# iso_lvds_rx.net
KiCad netlist of a schematic drawn in Altium Designer
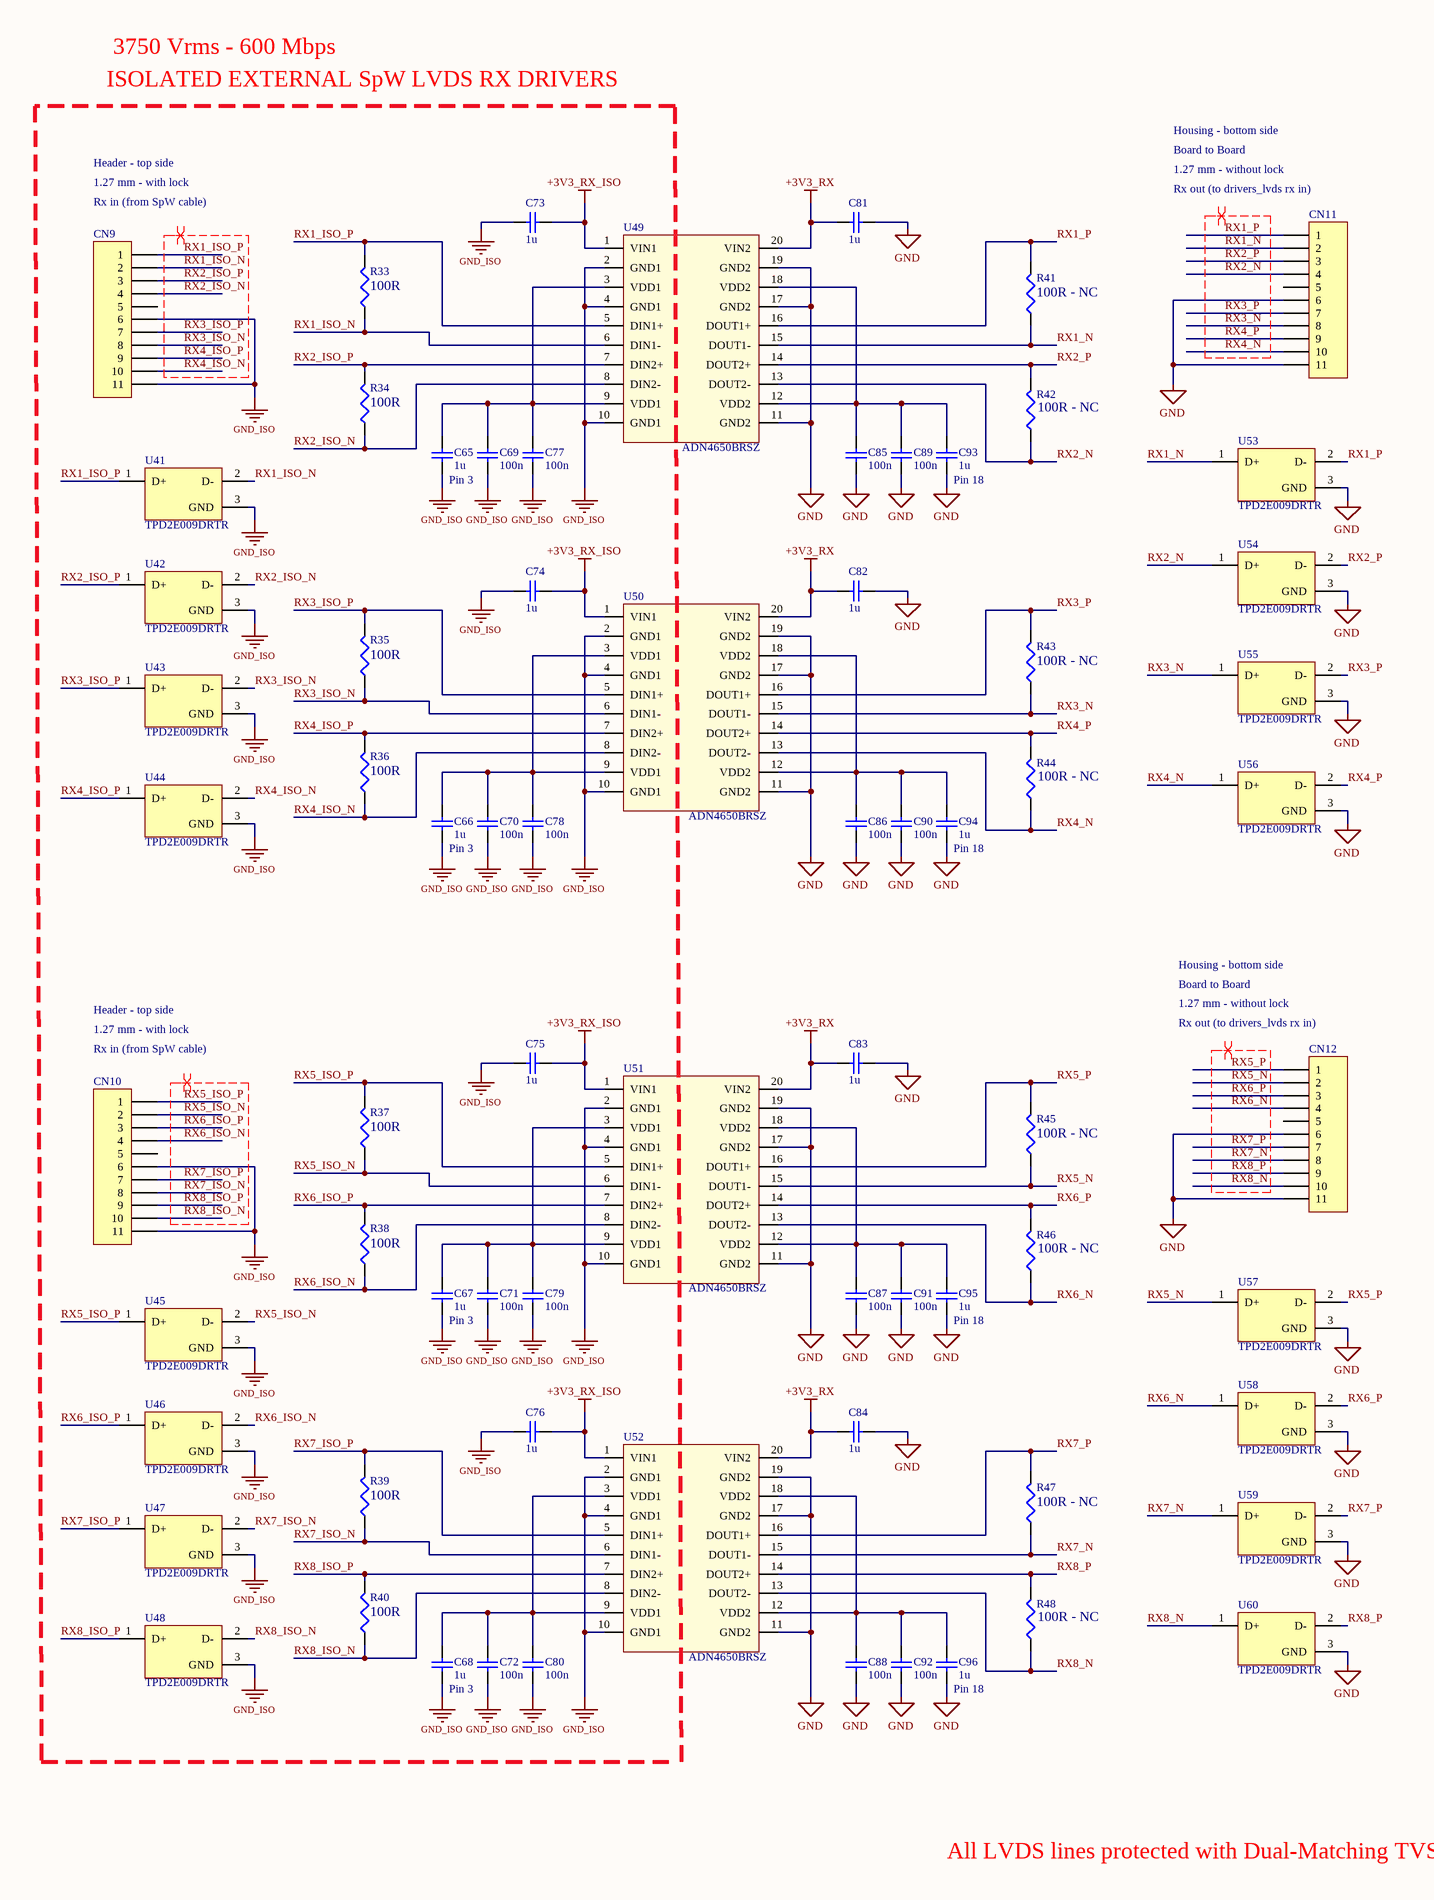
[diagram p0: iso_lvds_rx.SchDoc, left]
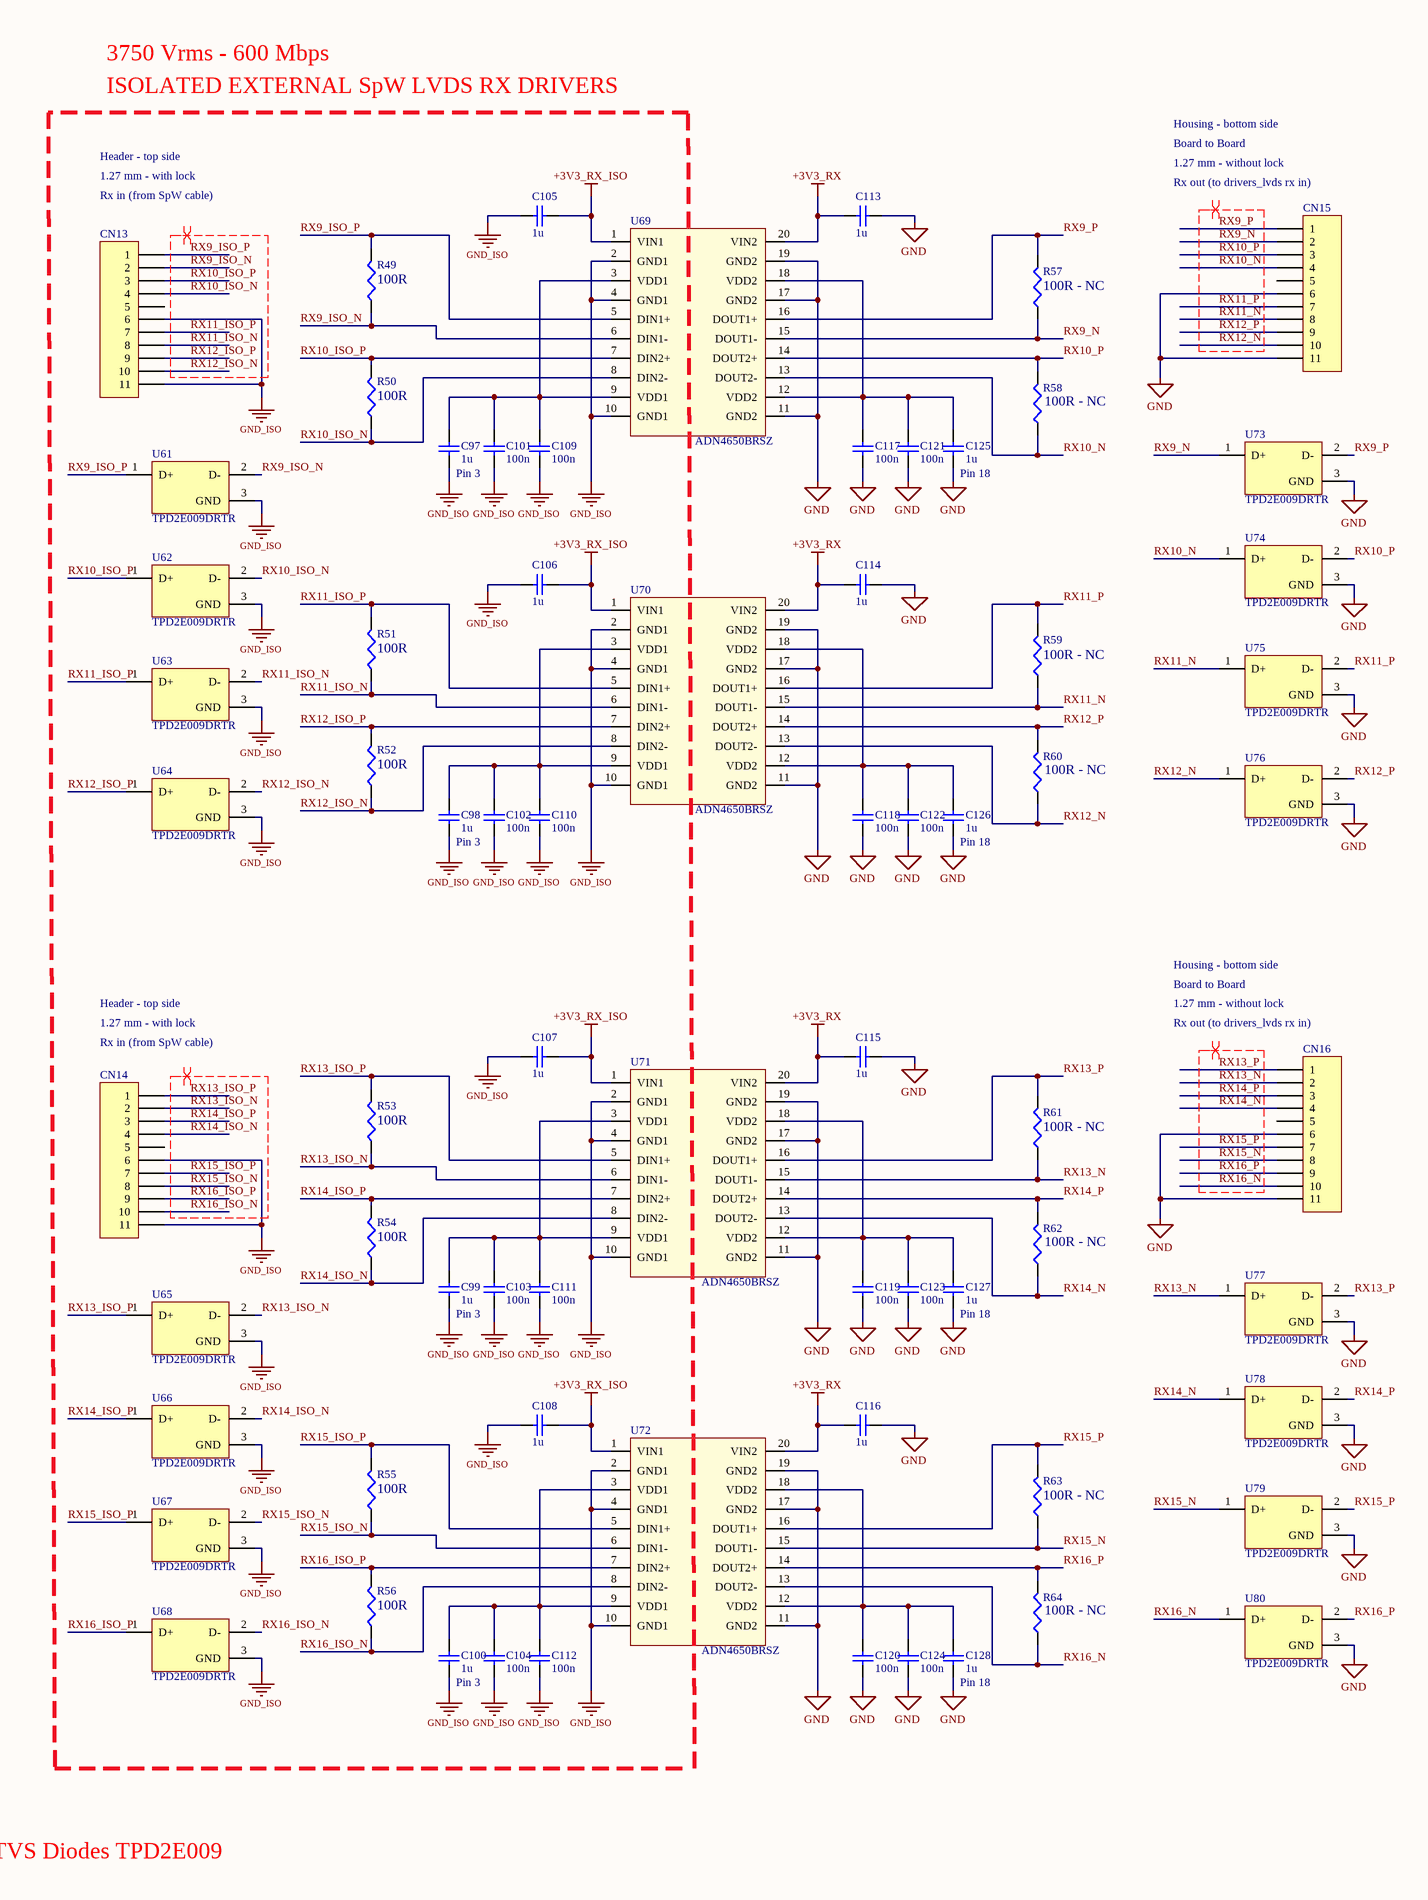
[diagram p1: iso_lvds_rx.SchDoc, right]

(export (version "E")
  (design (tool "Eeschema 10.0.6"))
  (components
    (comp (ref "C65")
      (value "Capacitor Cerâmico SMD")
      (footprint "0402-cap")
      (fields (field (name "VALOR") "1u"))
      (libsource (lib "Miscellaneous Devices") (part "Capacitor Cerâmico SMD"))
    )
    (comp (ref "C66")
      (value "Capacitor Cerâmico SMD")
      (footprint "0402-cap")
      (fields (field (name "VALOR") "1u"))
      (libsource (lib "Miscellaneous Devices") (part "Capacitor Cerâmico SMD"))
    )
    (comp (ref "C67")
      (value "Capacitor Cerâmico SMD")
      (footprint "0402-cap")
      (fields (field (name "VALOR") "1u"))
      (libsource (lib "Miscellaneous Devices") (part "Capacitor Cerâmico SMD"))
    )
    (comp (ref "C68")
      (value "Capacitor Cerâmico SMD")
      (footprint "0402-cap")
      (fields (field (name "VALOR") "1u"))
      (libsource (lib "Miscellaneous Devices") (part "Capacitor Cerâmico SMD"))
    )
    (comp (ref "C69")
      (value "Capacitor Cerâmico SMD")
      (footprint "0402-cap")
      (fields (field (name "VALOR") "100n"))
      (libsource (lib "Miscellaneous Devices") (part "Capacitor Cerâmico SMD"))
    )
    (comp (ref "C70")
      (value "Capacitor Cerâmico SMD")
      (footprint "0402-cap")
      (fields (field (name "VALOR") "100n"))
      (libsource (lib "Miscellaneous Devices") (part "Capacitor Cerâmico SMD"))
    )
    (comp (ref "C71")
      (value "Capacitor Cerâmico SMD")
      (footprint "0402-cap")
      (fields (field (name "VALOR") "100n"))
      (libsource (lib "Miscellaneous Devices") (part "Capacitor Cerâmico SMD"))
    )
    (comp (ref "C72")
      (value "Capacitor Cerâmico SMD")
      (footprint "0402-cap")
      (fields (field (name "VALOR") "100n"))
      (libsource (lib "Miscellaneous Devices") (part "Capacitor Cerâmico SMD"))
    )
    (comp (ref "C73")
      (value "Capacitor Cerâmico SMD")
      (footprint "0402-cap")
      (fields (field (name "VALOR") "1u"))
      (libsource (lib "Miscellaneous Devices") (part "Capacitor Cerâmico SMD"))
    )
    (comp (ref "C74")
      (value "Capacitor Cerâmico SMD")
      (footprint "0402-cap")
      (fields (field (name "VALOR") "1u"))
      (libsource (lib "Miscellaneous Devices") (part "Capacitor Cerâmico SMD"))
    )
    (comp (ref "C75")
      (value "Capacitor Cerâmico SMD")
      (footprint "0402-cap")
      (fields (field (name "VALOR") "1u"))
      (libsource (lib "Miscellaneous Devices") (part "Capacitor Cerâmico SMD"))
    )
    (comp (ref "C76")
      (value "Capacitor Cerâmico SMD")
      (footprint "0402-cap")
      (fields (field (name "VALOR") "1u"))
      (libsource (lib "Miscellaneous Devices") (part "Capacitor Cerâmico SMD"))
    )
    (comp (ref "C77")
      (value "Capacitor Cerâmico SMD")
      (footprint "0402-cap")
      (fields (field (name "VALOR") "100n"))
      (libsource (lib "Miscellaneous Devices") (part "Capacitor Cerâmico SMD"))
    )
    (comp (ref "C78")
      (value "Capacitor Cerâmico SMD")
      (footprint "0402-cap")
      (fields (field (name "VALOR") "100n"))
      (libsource (lib "Miscellaneous Devices") (part "Capacitor Cerâmico SMD"))
    )
    (comp (ref "C79")
      (value "Capacitor Cerâmico SMD")
      (footprint "0402-cap")
      (fields (field (name "VALOR") "100n"))
      (libsource (lib "Miscellaneous Devices") (part "Capacitor Cerâmico SMD"))
    )
    (comp (ref "C80")
      (value "Capacitor Cerâmico SMD")
      (footprint "0402-cap")
      (fields (field (name "VALOR") "100n"))
      (libsource (lib "Miscellaneous Devices") (part "Capacitor Cerâmico SMD"))
    )
    (comp (ref "C81")
      (value "Capacitor Cerâmico SMD")
      (footprint "0402-cap")
      (fields (field (name "VALOR") "1u"))
      (libsource (lib "Miscellaneous Devices") (part "Capacitor Cerâmico SMD"))
    )
    (comp (ref "C82")
      (value "Capacitor Cerâmico SMD")
      (footprint "0402-cap")
      (fields (field (name "VALOR") "1u"))
      (libsource (lib "Miscellaneous Devices") (part "Capacitor Cerâmico SMD"))
    )
    (comp (ref "C83")
      (value "Capacitor Cerâmico SMD")
      (footprint "0402-cap")
      (fields (field (name "VALOR") "1u"))
      (libsource (lib "Miscellaneous Devices") (part "Capacitor Cerâmico SMD"))
    )
    (comp (ref "C84")
      (value "Capacitor Cerâmico SMD")
      (footprint "0402-cap")
      (fields (field (name "VALOR") "1u"))
      (libsource (lib "Miscellaneous Devices") (part "Capacitor Cerâmico SMD"))
    )
    (comp (ref "C85")
      (value "Capacitor Cerâmico SMD")
      (footprint "0402-cap")
      (fields (field (name "VALOR") "100n"))
      (libsource (lib "Miscellaneous Devices") (part "Capacitor Cerâmico SMD"))
    )
    (comp (ref "C86")
      (value "Capacitor Cerâmico SMD")
      (footprint "0402-cap")
      (fields (field (name "VALOR") "100n"))
      (libsource (lib "Miscellaneous Devices") (part "Capacitor Cerâmico SMD"))
    )
    (comp (ref "C87")
      (value "Capacitor Cerâmico SMD")
      (footprint "0402-cap")
      (fields (field (name "VALOR") "100n"))
      (libsource (lib "Miscellaneous Devices") (part "Capacitor Cerâmico SMD"))
    )
    (comp (ref "C88")
      (value "Capacitor Cerâmico SMD")
      (footprint "0402-cap")
      (fields (field (name "VALOR") "100n"))
      (libsource (lib "Miscellaneous Devices") (part "Capacitor Cerâmico SMD"))
    )
    (comp (ref "C89")
      (value "Capacitor Cerâmico SMD")
      (footprint "0402-cap")
      (fields (field (name "VALOR") "100n"))
      (libsource (lib "Miscellaneous Devices") (part "Capacitor Cerâmico SMD"))
    )
    (comp (ref "C90")
      (value "Capacitor Cerâmico SMD")
      (footprint "0402-cap")
      (fields (field (name "VALOR") "100n"))
      (libsource (lib "Miscellaneous Devices") (part "Capacitor Cerâmico SMD"))
    )
    (comp (ref "C91")
      (value "Capacitor Cerâmico SMD")
      (footprint "0402-cap")
      (fields (field (name "VALOR") "100n"))
      (libsource (lib "Miscellaneous Devices") (part "Capacitor Cerâmico SMD"))
    )
    (comp (ref "C92")
      (value "Capacitor Cerâmico SMD")
      (footprint "0402-cap")
      (fields (field (name "VALOR") "100n"))
      (libsource (lib "Miscellaneous Devices") (part "Capacitor Cerâmico SMD"))
    )
    (comp (ref "C93")
      (value "Capacitor Cerâmico SMD")
      (footprint "0402-cap")
      (fields (field (name "VALOR") "1u"))
      (libsource (lib "Miscellaneous Devices") (part "Capacitor Cerâmico SMD"))
    )
    (comp (ref "C94")
      (value "Capacitor Cerâmico SMD")
      (footprint "0402-cap")
      (fields (field (name "VALOR") "1u"))
      (libsource (lib "Miscellaneous Devices") (part "Capacitor Cerâmico SMD"))
    )
    (comp (ref "C95")
      (value "Capacitor Cerâmico SMD")
      (footprint "0402-cap")
      (fields (field (name "VALOR") "1u"))
      (libsource (lib "Miscellaneous Devices") (part "Capacitor Cerâmico SMD"))
    )
    (comp (ref "C96")
      (value "Capacitor Cerâmico SMD")
      (footprint "0402-cap")
      (fields (field (name "VALOR") "1u"))
      (libsource (lib "Miscellaneous Devices") (part "Capacitor Cerâmico SMD"))
    )
    (comp (ref "C97")
      (value "Capacitor Cerâmico SMD")
      (footprint "0402-cap")
      (fields (field (name "VALOR") "1u"))
      (libsource (lib "Miscellaneous Devices") (part "Capacitor Cerâmico SMD"))
    )
    (comp (ref "C98")
      (value "Capacitor Cerâmico SMD")
      (footprint "0402-cap")
      (fields (field (name "VALOR") "1u"))
      (libsource (lib "Miscellaneous Devices") (part "Capacitor Cerâmico SMD"))
    )
    (comp (ref "C99")
      (value "Capacitor Cerâmico SMD")
      (footprint "0402-cap")
      (fields (field (name "VALOR") "1u"))
      (libsource (lib "Miscellaneous Devices") (part "Capacitor Cerâmico SMD"))
    )
    (comp (ref "C100")
      (value "Capacitor Cerâmico SMD")
      (footprint "0402-cap")
      (fields (field (name "VALOR") "1u"))
      (libsource (lib "Miscellaneous Devices") (part "Capacitor Cerâmico SMD"))
    )
    (comp (ref "C101")
      (value "Capacitor Cerâmico SMD")
      (footprint "0402-cap")
      (fields (field (name "VALOR") "100n"))
      (libsource (lib "Miscellaneous Devices") (part "Capacitor Cerâmico SMD"))
    )
    (comp (ref "C102")
      (value "Capacitor Cerâmico SMD")
      (footprint "0402-cap")
      (fields (field (name "VALOR") "100n"))
      (libsource (lib "Miscellaneous Devices") (part "Capacitor Cerâmico SMD"))
    )
    (comp (ref "C103")
      (value "Capacitor Cerâmico SMD")
      (footprint "0402-cap")
      (fields (field (name "VALOR") "100n"))
      (libsource (lib "Miscellaneous Devices") (part "Capacitor Cerâmico SMD"))
    )
    (comp (ref "C104")
      (value "Capacitor Cerâmico SMD")
      (footprint "0402-cap")
      (fields (field (name "VALOR") "100n"))
      (libsource (lib "Miscellaneous Devices") (part "Capacitor Cerâmico SMD"))
    )
    (comp (ref "C105")
      (value "Capacitor Cerâmico SMD")
      (footprint "0402-cap")
      (fields (field (name "VALOR") "1u"))
      (libsource (lib "Miscellaneous Devices") (part "Capacitor Cerâmico SMD"))
    )
    (comp (ref "C106")
      (value "Capacitor Cerâmico SMD")
      (footprint "0402-cap")
      (fields (field (name "VALOR") "1u"))
      (libsource (lib "Miscellaneous Devices") (part "Capacitor Cerâmico SMD"))
    )
    (comp (ref "C107")
      (value "Capacitor Cerâmico SMD")
      (footprint "0402-cap")
      (fields (field (name "VALOR") "1u"))
      (libsource (lib "Miscellaneous Devices") (part "Capacitor Cerâmico SMD"))
    )
    (comp (ref "C108")
      (value "Capacitor Cerâmico SMD")
      (footprint "0402-cap")
      (fields (field (name "VALOR") "1u"))
      (libsource (lib "Miscellaneous Devices") (part "Capacitor Cerâmico SMD"))
    )
    (comp (ref "C109")
      (value "Capacitor Cerâmico SMD")
      (footprint "0402-cap")
      (fields (field (name "VALOR") "100n"))
      (libsource (lib "Miscellaneous Devices") (part "Capacitor Cerâmico SMD"))
    )
    (comp (ref "C110")
      (value "Capacitor Cerâmico SMD")
      (footprint "0402-cap")
      (fields (field (name "VALOR") "100n"))
      (libsource (lib "Miscellaneous Devices") (part "Capacitor Cerâmico SMD"))
    )
    (comp (ref "C111")
      (value "Capacitor Cerâmico SMD")
      (footprint "0402-cap")
      (fields (field (name "VALOR") "100n"))
      (libsource (lib "Miscellaneous Devices") (part "Capacitor Cerâmico SMD"))
    )
    (comp (ref "C112")
      (value "Capacitor Cerâmico SMD")
      (footprint "0402-cap")
      (fields (field (name "VALOR") "100n"))
      (libsource (lib "Miscellaneous Devices") (part "Capacitor Cerâmico SMD"))
    )
    (comp (ref "C113")
      (value "Capacitor Cerâmico SMD")
      (footprint "0402-cap")
      (fields (field (name "VALOR") "1u"))
      (libsource (lib "Miscellaneous Devices") (part "Capacitor Cerâmico SMD"))
    )
    (comp (ref "C114")
      (value "Capacitor Cerâmico SMD")
      (footprint "0402-cap")
      (fields (field (name "VALOR") "1u"))
      (libsource (lib "Miscellaneous Devices") (part "Capacitor Cerâmico SMD"))
    )
    (comp (ref "C115")
      (value "Capacitor Cerâmico SMD")
      (footprint "0402-cap")
      (fields (field (name "VALOR") "1u"))
      (libsource (lib "Miscellaneous Devices") (part "Capacitor Cerâmico SMD"))
    )
    (comp (ref "C116")
      (value "Capacitor Cerâmico SMD")
      (footprint "0402-cap")
      (fields (field (name "VALOR") "1u"))
      (libsource (lib "Miscellaneous Devices") (part "Capacitor Cerâmico SMD"))
    )
    (comp (ref "C117")
      (value "Capacitor Cerâmico SMD")
      (footprint "0402-cap")
      (fields (field (name "VALOR") "100n"))
      (libsource (lib "Miscellaneous Devices") (part "Capacitor Cerâmico SMD"))
    )
    (comp (ref "C118")
      (value "Capacitor Cerâmico SMD")
      (footprint "0402-cap")
      (fields (field (name "VALOR") "100n"))
      (libsource (lib "Miscellaneous Devices") (part "Capacitor Cerâmico SMD"))
    )
    (comp (ref "C119")
      (value "Capacitor Cerâmico SMD")
      (footprint "0402-cap")
      (fields (field (name "VALOR") "100n"))
      (libsource (lib "Miscellaneous Devices") (part "Capacitor Cerâmico SMD"))
    )
    (comp (ref "C120")
      (value "Capacitor Cerâmico SMD")
      (footprint "0402-cap")
      (fields (field (name "VALOR") "100n"))
      (libsource (lib "Miscellaneous Devices") (part "Capacitor Cerâmico SMD"))
    )
    (comp (ref "C121")
      (value "Capacitor Cerâmico SMD")
      (footprint "0402-cap")
      (fields (field (name "VALOR") "100n"))
      (libsource (lib "Miscellaneous Devices") (part "Capacitor Cerâmico SMD"))
    )
    (comp (ref "C122")
      (value "Capacitor Cerâmico SMD")
      (footprint "0402-cap")
      (fields (field (name "VALOR") "100n"))
      (libsource (lib "Miscellaneous Devices") (part "Capacitor Cerâmico SMD"))
    )
    (comp (ref "C123")
      (value "Capacitor Cerâmico SMD")
      (footprint "0402-cap")
      (fields (field (name "VALOR") "100n"))
      (libsource (lib "Miscellaneous Devices") (part "Capacitor Cerâmico SMD"))
    )
    (comp (ref "C124")
      (value "Capacitor Cerâmico SMD")
      (footprint "0402-cap")
      (fields (field (name "VALOR") "100n"))
      (libsource (lib "Miscellaneous Devices") (part "Capacitor Cerâmico SMD"))
    )
    (comp (ref "C125")
      (value "Capacitor Cerâmico SMD")
      (footprint "0402-cap")
      (fields (field (name "VALOR") "1u"))
      (libsource (lib "Miscellaneous Devices") (part "Capacitor Cerâmico SMD"))
    )
    (comp (ref "C126")
      (value "Capacitor Cerâmico SMD")
      (footprint "0402-cap")
      (fields (field (name "VALOR") "1u"))
      (libsource (lib "Miscellaneous Devices") (part "Capacitor Cerâmico SMD"))
    )
    (comp (ref "C127")
      (value "Capacitor Cerâmico SMD")
      (footprint "0402-cap")
      (fields (field (name "VALOR") "1u"))
      (libsource (lib "Miscellaneous Devices") (part "Capacitor Cerâmico SMD"))
    )
    (comp (ref "C128")
      (value "Capacitor Cerâmico SMD")
      (footprint "0402-cap")
      (fields (field (name "VALOR") "1u"))
      (libsource (lib "Miscellaneous Devices") (part "Capacitor Cerâmico SMD"))
    )
    (comp (ref "CN9")
      (value "MHDR1X11")
      (footprint "MHDR1X11_Axonn")
      (description "Header, 11-Pin")
      (fields (field (name "PUBLISHER") "Altium Limited"))
      (libsource (lib "") (part "MHDR1X11_1"))
    )
    (comp (ref "CN10")
      (value "MHDR1X11")
      (footprint "MHDR1X11_Axonn")
      (description "Header, 11-Pin")
      (fields (field (name "PUBLISHER") "Altium Limited"))
      (libsource (lib "") (part "MHDR1X11_1"))
    )
    (comp (ref "CN11")
      (value "MHDR1X11")
      (footprint "MHDR1X11_Axonn")
      (description "Header, 11-Pin")
      (fields (field (name "PUBLISHER") "Altium Limited"))
      (libsource (lib "Miscellaneous Connectors") (part "MHDR1X11"))
    )
    (comp (ref "CN12")
      (value "MHDR1X11")
      (footprint "MHDR1X11_Axonn")
      (description "Header, 11-Pin")
      (fields (field (name "PUBLISHER") "Altium Limited"))
      (libsource (lib "Miscellaneous Connectors") (part "MHDR1X11"))
    )
    (comp (ref "CN13")
      (value "MHDR1X11")
      (footprint "MHDR1X11_Axonn")
      (description "Header, 11-Pin")
      (fields (field (name "PUBLISHER") "Altium Limited"))
      (libsource (lib "") (part "MHDR1X11_1"))
    )
    (comp (ref "CN14")
      (value "MHDR1X11")
      (footprint "MHDR1X11_Axonn")
      (description "Header, 11-Pin")
      (fields (field (name "PUBLISHER") "Altium Limited"))
      (libsource (lib "") (part "MHDR1X11_1"))
    )
    (comp (ref "CN15")
      (value "MHDR1X11")
      (footprint "MHDR1X11_Axonn")
      (description "Header, 11-Pin")
      (fields (field (name "PUBLISHER") "Altium Limited"))
      (libsource (lib "Miscellaneous Connectors") (part "MHDR1X11"))
    )
    (comp (ref "CN16")
      (value "MHDR1X11")
      (footprint "MHDR1X11_Axonn")
      (description "Header, 11-Pin")
      (fields (field (name "PUBLISHER") "Altium Limited"))
      (libsource (lib "Miscellaneous Connectors") (part "MHDR1X11"))
    )
    (comp (ref "R33")
      (value "Res3")
      (footprint "0402-res")
      (description "Resistor")
      (fields (field (name "VALOR") "100R"))
      (libsource (lib "Miscellaneous Devices") (part "Res3"))
    )
    (comp (ref "R34")
      (value "Res3")
      (footprint "0402-res")
      (description "Resistor")
      (fields (field (name "VALOR") "100R"))
      (libsource (lib "Miscellaneous Devices") (part "Res3"))
    )
    (comp (ref "R35")
      (value "Res3")
      (footprint "0402-res")
      (description "Resistor")
      (fields (field (name "VALOR") "100R"))
      (libsource (lib "Miscellaneous Devices") (part "Res3"))
    )
    (comp (ref "R36")
      (value "Res3")
      (footprint "0402-res")
      (description "Resistor")
      (fields (field (name "VALOR") "100R"))
      (libsource (lib "Miscellaneous Devices") (part "Res3"))
    )
    (comp (ref "R37")
      (value "Res3")
      (footprint "0402-res")
      (description "Resistor")
      (fields (field (name "VALOR") "100R"))
      (libsource (lib "Miscellaneous Devices") (part "Res3"))
    )
    (comp (ref "R38")
      (value "Res3")
      (footprint "0402-res")
      (description "Resistor")
      (fields (field (name "VALOR") "100R"))
      (libsource (lib "Miscellaneous Devices") (part "Res3"))
    )
    (comp (ref "R39")
      (value "Res3")
      (footprint "0402-res")
      (description "Resistor")
      (fields (field (name "VALOR") "100R"))
      (libsource (lib "Miscellaneous Devices") (part "Res3"))
    )
    (comp (ref "R40")
      (value "Res3")
      (footprint "0402-res")
      (description "Resistor")
      (fields (field (name "VALOR") "100R"))
      (libsource (lib "Miscellaneous Devices") (part "Res3"))
    )
    (comp (ref "R41")
      (value "Res3")
      (footprint "0402-res")
      (description "Resistor")
      (fields (field (name "VALOR") "100R - NC"))
      (libsource (lib "Miscellaneous Devices") (part "Res3"))
    )
    (comp (ref "R42")
      (value "Res3")
      (footprint "0402-res")
      (description "Resistor")
      (fields (field (name "VALOR") "100R - NC"))
      (libsource (lib "Miscellaneous Devices") (part "Res3"))
    )
    (comp (ref "R43")
      (value "Res3")
      (footprint "0402-res")
      (description "Resistor")
      (fields (field (name "VALOR") "100R - NC"))
      (libsource (lib "Miscellaneous Devices") (part "Res3"))
    )
    (comp (ref "R44")
      (value "Res3")
      (footprint "0402-res")
      (description "Resistor")
      (fields (field (name "VALOR") "100R - NC"))
      (libsource (lib "Miscellaneous Devices") (part "Res3"))
    )
    (comp (ref "R45")
      (value "Res3")
      (footprint "0402-res")
      (description "Resistor")
      (fields (field (name "VALOR") "100R - NC"))
      (libsource (lib "Miscellaneous Devices") (part "Res3"))
    )
    (comp (ref "R46")
      (value "Res3")
      (footprint "0402-res")
      (description "Resistor")
      (fields (field (name "VALOR") "100R - NC"))
      (libsource (lib "Miscellaneous Devices") (part "Res3"))
    )
    (comp (ref "R47")
      (value "Res3")
      (footprint "0402-res")
      (description "Resistor")
      (fields (field (name "VALOR") "100R - NC"))
      (libsource (lib "Miscellaneous Devices") (part "Res3"))
    )
    (comp (ref "R48")
      (value "Res3")
      (footprint "0402-res")
      (description "Resistor")
      (fields (field (name "VALOR") "100R - NC"))
      (libsource (lib "Miscellaneous Devices") (part "Res3"))
    )
    (comp (ref "R49")
      (value "Res3")
      (footprint "0402-res")
      (description "Resistor")
      (fields (field (name "VALOR") "100R"))
      (libsource (lib "Miscellaneous Devices") (part "Res3"))
    )
    (comp (ref "R50")
      (value "Res3")
      (footprint "0402-res")
      (description "Resistor")
      (fields (field (name "VALOR") "100R"))
      (libsource (lib "Miscellaneous Devices") (part "Res3"))
    )
    (comp (ref "R51")
      (value "Res3")
      (footprint "0402-res")
      (description "Resistor")
      (fields (field (name "VALOR") "100R"))
      (libsource (lib "Miscellaneous Devices") (part "Res3"))
    )
    (comp (ref "R52")
      (value "Res3")
      (footprint "0402-res")
      (description "Resistor")
      (fields (field (name "VALOR") "100R"))
      (libsource (lib "Miscellaneous Devices") (part "Res3"))
    )
    (comp (ref "R53")
      (value "Res3")
      (footprint "0402-res")
      (description "Resistor")
      (fields (field (name "VALOR") "100R"))
      (libsource (lib "Miscellaneous Devices") (part "Res3"))
    )
    (comp (ref "R54")
      (value "Res3")
      (footprint "0402-res")
      (description "Resistor")
      (fields (field (name "VALOR") "100R"))
      (libsource (lib "Miscellaneous Devices") (part "Res3"))
    )
    (comp (ref "R55")
      (value "Res3")
      (footprint "0402-res")
      (description "Resistor")
      (fields (field (name "VALOR") "100R"))
      (libsource (lib "Miscellaneous Devices") (part "Res3"))
    )
    (comp (ref "R56")
      (value "Res3")
      (footprint "0402-res")
      (description "Resistor")
      (fields (field (name "VALOR") "100R"))
      (libsource (lib "Miscellaneous Devices") (part "Res3"))
    )
    (comp (ref "R57")
      (value "Res3")
      (footprint "0402-res")
      (description "Resistor")
      (fields (field (name "VALOR") "100R - NC"))
      (libsource (lib "Miscellaneous Devices") (part "Res3"))
    )
    (comp (ref "R58")
      (value "Res3")
      (footprint "0402-res")
      (description "Resistor")
      (fields (field (name "VALOR") "100R - NC"))
      (libsource (lib "Miscellaneous Devices") (part "Res3"))
    )
    (comp (ref "R59")
      (value "Res3")
      (footprint "0402-res")
      (description "Resistor")
      (fields (field (name "VALOR") "100R - NC"))
      (libsource (lib "Miscellaneous Devices") (part "Res3"))
    )
    (comp (ref "R60")
      (value "Res3")
      (footprint "0402-res")
      (description "Resistor")
      (fields (field (name "VALOR") "100R - NC"))
      (libsource (lib "Miscellaneous Devices") (part "Res3"))
    )
    (comp (ref "R61")
      (value "Res3")
      (footprint "0402-res")
      (description "Resistor")
      (fields (field (name "VALOR") "100R - NC"))
      (libsource (lib "Miscellaneous Devices") (part "Res3"))
    )
    (comp (ref "R62")
      (value "Res3")
      (footprint "0402-res")
      (description "Resistor")
      (fields (field (name "VALOR") "100R - NC"))
      (libsource (lib "Miscellaneous Devices") (part "Res3"))
    )
    (comp (ref "R63")
      (value "Res3")
      (footprint "0402-res")
      (description "Resistor")
      (fields (field (name "VALOR") "100R - NC"))
      (libsource (lib "Miscellaneous Devices") (part "Res3"))
    )
    (comp (ref "R64")
      (value "Res3")
      (footprint "0402-res")
      (description "Resistor")
      (fields (field (name "VALOR") "100R - NC"))
      (libsource (lib "Miscellaneous Devices") (part "Res3"))
    )
    (comp (ref "U41")
      (value "TPD2E009DRTR")
      (footprint "DRT3")
      (fields (field (name "MANUFACTURER") "Texas Instruments"))
      (libsource (lib "TI Interface ESD EMI Protection") (part "TPD2E009DRTR"))
    )
    (comp (ref "U42")
      (value "TPD2E009DRTR")
      (footprint "DRT3")
      (fields (field (name "MANUFACTURER") "Texas Instruments"))
      (libsource (lib "TI Interface ESD EMI Protection") (part "TPD2E009DRTR"))
    )
    (comp (ref "U43")
      (value "TPD2E009DRTR")
      (footprint "DRT3")
      (fields (field (name "MANUFACTURER") "Texas Instruments"))
      (libsource (lib "TI Interface ESD EMI Protection") (part "TPD2E009DRTR"))
    )
    (comp (ref "U44")
      (value "TPD2E009DRTR")
      (footprint "DRT3")
      (fields (field (name "MANUFACTURER") "Texas Instruments"))
      (libsource (lib "TI Interface ESD EMI Protection") (part "TPD2E009DRTR"))
    )
    (comp (ref "U45")
      (value "TPD2E009DRTR")
      (footprint "DRT3")
      (fields (field (name "MANUFACTURER") "Texas Instruments"))
      (libsource (lib "TI Interface ESD EMI Protection") (part "TPD2E009DRTR"))
    )
    (comp (ref "U46")
      (value "TPD2E009DRTR")
      (footprint "DRT3")
      (fields (field (name "MANUFACTURER") "Texas Instruments"))
      (libsource (lib "TI Interface ESD EMI Protection") (part "TPD2E009DRTR"))
    )
    (comp (ref "U47")
      (value "TPD2E009DRTR")
      (footprint "DRT3")
      (fields (field (name "MANUFACTURER") "Texas Instruments"))
      (libsource (lib "TI Interface ESD EMI Protection") (part "TPD2E009DRTR"))
    )
    (comp (ref "U48")
      (value "TPD2E009DRTR")
      (footprint "DRT3")
      (fields (field (name "MANUFACTURER") "Texas Instruments"))
      (libsource (lib "TI Interface ESD EMI Protection") (part "TPD2E009DRTR"))
    )
    (comp (ref "U49")
      (value "ADN4650BRSZ")
      (footprint "SSOP-RS-20")
      (description "5 kV RMS/3.75 kV RMS, 600 Mbps,  Dual-Channel LVDS Isolators")
      (fields (field (name "PART NUMBER") "ADN4650BRSZ"))
      (libsource (lib "lvds_isolators") (part "ADN4650BRSZ"))
    )
    (comp (ref "U50")
      (value "ADN4650BRSZ")
      (footprint "SSOP-RS-20")
      (description "5 kV RMS/3.75 kV RMS, 600 Mbps,  Dual-Channel LVDS Isolators")
      (fields (field (name "PART NUMBER") "ADN4650BRSZ"))
      (libsource (lib "lvds_isolators") (part "ADN4650BRSZ"))
    )
    (comp (ref "U51")
      (value "ADN4650BRSZ")
      (footprint "SSOP-RS-20")
      (description "5 kV RMS/3.75 kV RMS, 600 Mbps,  Dual-Channel LVDS Isolators")
      (fields (field (name "PART NUMBER") "ADN4650BRSZ"))
      (libsource (lib "lvds_isolators") (part "ADN4650BRSZ"))
    )
    (comp (ref "U52")
      (value "ADN4650BRSZ")
      (footprint "SSOP-RS-20")
      (description "5 kV RMS/3.75 kV RMS, 600 Mbps,  Dual-Channel LVDS Isolators")
      (fields (field (name "PART NUMBER") "ADN4650BRSZ"))
      (libsource (lib "lvds_isolators") (part "ADN4650BRSZ"))
    )
    (comp (ref "U53")
      (value "TPD2E009DRTR")
      (footprint "DRT3")
      (fields (field (name "MANUFACTURER") "Texas Instruments"))
      (libsource (lib "TI Interface ESD EMI Protection") (part "TPD2E009DRTR"))
    )
    (comp (ref "U54")
      (value "TPD2E009DRTR")
      (footprint "DRT3")
      (fields (field (name "MANUFACTURER") "Texas Instruments"))
      (libsource (lib "TI Interface ESD EMI Protection") (part "TPD2E009DRTR"))
    )
    (comp (ref "U55")
      (value "TPD2E009DRTR")
      (footprint "DRT3")
      (fields (field (name "MANUFACTURER") "Texas Instruments"))
      (libsource (lib "TI Interface ESD EMI Protection") (part "TPD2E009DRTR"))
    )
    (comp (ref "U56")
      (value "TPD2E009DRTR")
      (footprint "DRT3")
      (fields (field (name "MANUFACTURER") "Texas Instruments"))
      (libsource (lib "TI Interface ESD EMI Protection") (part "TPD2E009DRTR"))
    )
    (comp (ref "U57")
      (value "TPD2E009DRTR")
      (footprint "DRT3")
      (fields (field (name "MANUFACTURER") "Texas Instruments"))
      (libsource (lib "TI Interface ESD EMI Protection") (part "TPD2E009DRTR"))
    )
    (comp (ref "U58")
      (value "TPD2E009DRTR")
      (footprint "DRT3")
      (fields (field (name "MANUFACTURER") "Texas Instruments"))
      (libsource (lib "TI Interface ESD EMI Protection") (part "TPD2E009DRTR"))
    )
    (comp (ref "U59")
      (value "TPD2E009DRTR")
      (footprint "DRT3")
      (fields (field (name "MANUFACTURER") "Texas Instruments"))
      (libsource (lib "TI Interface ESD EMI Protection") (part "TPD2E009DRTR"))
    )
    (comp (ref "U60")
      (value "TPD2E009DRTR")
      (footprint "DRT3")
      (fields (field (name "MANUFACTURER") "Texas Instruments"))
      (libsource (lib "TI Interface ESD EMI Protection") (part "TPD2E009DRTR"))
    )
    (comp (ref "U61")
      (value "TPD2E009DRTR")
      (footprint "DRT3")
      (fields (field (name "MANUFACTURER") "Texas Instruments"))
      (libsource (lib "TI Interface ESD EMI Protection") (part "TPD2E009DRTR"))
    )
    (comp (ref "U62")
      (value "TPD2E009DRTR")
      (footprint "DRT3")
      (fields (field (name "MANUFACTURER") "Texas Instruments"))
      (libsource (lib "TI Interface ESD EMI Protection") (part "TPD2E009DRTR"))
    )
    (comp (ref "U63")
      (value "TPD2E009DRTR")
      (footprint "DRT3")
      (fields (field (name "MANUFACTURER") "Texas Instruments"))
      (libsource (lib "TI Interface ESD EMI Protection") (part "TPD2E009DRTR"))
    )
    (comp (ref "U64")
      (value "TPD2E009DRTR")
      (footprint "DRT3")
      (fields (field (name "MANUFACTURER") "Texas Instruments"))
      (libsource (lib "TI Interface ESD EMI Protection") (part "TPD2E009DRTR"))
    )
    (comp (ref "U65")
      (value "TPD2E009DRTR")
      (footprint "DRT3")
      (fields (field (name "MANUFACTURER") "Texas Instruments"))
      (libsource (lib "TI Interface ESD EMI Protection") (part "TPD2E009DRTR"))
    )
    (comp (ref "U66")
      (value "TPD2E009DRTR")
      (footprint "DRT3")
      (fields (field (name "MANUFACTURER") "Texas Instruments"))
      (libsource (lib "TI Interface ESD EMI Protection") (part "TPD2E009DRTR"))
    )
    (comp (ref "U67")
      (value "TPD2E009DRTR")
      (footprint "DRT3")
      (fields (field (name "MANUFACTURER") "Texas Instruments"))
      (libsource (lib "TI Interface ESD EMI Protection") (part "TPD2E009DRTR"))
    )
    (comp (ref "U68")
      (value "TPD2E009DRTR")
      (footprint "DRT3")
      (fields (field (name "MANUFACTURER") "Texas Instruments"))
      (libsource (lib "TI Interface ESD EMI Protection") (part "TPD2E009DRTR"))
    )
    (comp (ref "U69")
      (value "ADN4650BRSZ")
      (footprint "SSOP-RS-20")
      (description "5 kV RMS/3.75 kV RMS, 600 Mbps,  Dual-Channel LVDS Isolators")
      (fields (field (name "PART NUMBER") "ADN4650BRSZ"))
      (libsource (lib "lvds_isolators") (part "ADN4650BRSZ"))
    )
    (comp (ref "U70")
      (value "ADN4650BRSZ")
      (footprint "SSOP-RS-20")
      (description "5 kV RMS/3.75 kV RMS, 600 Mbps,  Dual-Channel LVDS Isolators")
      (fields (field (name "PART NUMBER") "ADN4650BRSZ"))
      (libsource (lib "lvds_isolators") (part "ADN4650BRSZ"))
    )
    (comp (ref "U71")
      (value "ADN4650BRSZ")
      (footprint "SSOP-RS-20")
      (description "5 kV RMS/3.75 kV RMS, 600 Mbps,  Dual-Channel LVDS Isolators")
      (fields (field (name "PART NUMBER") "ADN4650BRSZ"))
      (libsource (lib "lvds_isolators") (part "ADN4650BRSZ"))
    )
    (comp (ref "U72")
      (value "ADN4650BRSZ")
      (footprint "SSOP-RS-20")
      (description "5 kV RMS/3.75 kV RMS, 600 Mbps,  Dual-Channel LVDS Isolators")
      (fields (field (name "PART NUMBER") "ADN4650BRSZ"))
      (libsource (lib "lvds_isolators") (part "ADN4650BRSZ"))
    )
    (comp (ref "U73")
      (value "TPD2E009DRTR")
      (footprint "DRT3")
      (fields (field (name "MANUFACTURER") "Texas Instruments"))
      (libsource (lib "TI Interface ESD EMI Protection") (part "TPD2E009DRTR"))
    )
    (comp (ref "U74")
      (value "TPD2E009DRTR")
      (footprint "DRT3")
      (fields (field (name "MANUFACTURER") "Texas Instruments"))
      (libsource (lib "TI Interface ESD EMI Protection") (part "TPD2E009DRTR"))
    )
    (comp (ref "U75")
      (value "TPD2E009DRTR")
      (footprint "DRT3")
      (fields (field (name "MANUFACTURER") "Texas Instruments"))
      (libsource (lib "TI Interface ESD EMI Protection") (part "TPD2E009DRTR"))
    )
    (comp (ref "U76")
      (value "TPD2E009DRTR")
      (footprint "DRT3")
      (fields (field (name "MANUFACTURER") "Texas Instruments"))
      (libsource (lib "TI Interface ESD EMI Protection") (part "TPD2E009DRTR"))
    )
    (comp (ref "U77")
      (value "TPD2E009DRTR")
      (footprint "DRT3")
      (fields (field (name "MANUFACTURER") "Texas Instruments"))
      (libsource (lib "TI Interface ESD EMI Protection") (part "TPD2E009DRTR"))
    )
    (comp (ref "U78")
      (value "TPD2E009DRTR")
      (footprint "DRT3")
      (fields (field (name "MANUFACTURER") "Texas Instruments"))
      (libsource (lib "TI Interface ESD EMI Protection") (part "TPD2E009DRTR"))
    )
    (comp (ref "U79")
      (value "TPD2E009DRTR")
      (footprint "DRT3")
      (fields (field (name "MANUFACTURER") "Texas Instruments"))
      (libsource (lib "TI Interface ESD EMI Protection") (part "TPD2E009DRTR"))
    )
    (comp (ref "U80")
      (value "TPD2E009DRTR")
      (footprint "DRT3")
      (fields (field (name "MANUFACTURER") "Texas Instruments"))
      (libsource (lib "TI Interface ESD EMI Protection") (part "TPD2E009DRTR"))
    )
  )
  (nets
    (net (code "1") (name "+3V3_RX") (class "Default")
      (node (ref "C113") (pin "2") (pinfunction "2_2") (pintype "passive"))
      (node (ref "C114") (pin "2") (pinfunction "2_2") (pintype "passive"))
      (node (ref "C115") (pin "2") (pinfunction "2_2") (pintype "passive"))
      (node (ref "C116") (pin "2") (pinfunction "2_2") (pintype "passive"))
      (node (ref "C81") (pin "2") (pinfunction "2_2") (pintype "passive"))
      (node (ref "C82") (pin "2") (pinfunction "2_2") (pintype "passive"))
      (node (ref "C83") (pin "2") (pinfunction "2_2") (pintype "passive"))
      (node (ref "C84") (pin "2") (pinfunction "2_2") (pintype "passive"))
      (node (ref "U49") (pin "20") (pinfunction "VIN2_20") (pintype "passive"))
      (node (ref "U50") (pin "20") (pinfunction "VIN2_20") (pintype "passive"))
      (node (ref "U51") (pin "20") (pinfunction "VIN2_20") (pintype "passive"))
      (node (ref "U52") (pin "20") (pinfunction "VIN2_20") (pintype "passive"))
      (node (ref "U69") (pin "20") (pinfunction "VIN2_20") (pintype "passive"))
      (node (ref "U70") (pin "20") (pinfunction "VIN2_20") (pintype "passive"))
      (node (ref "U71") (pin "20") (pinfunction "VIN2_20") (pintype "passive"))
      (node (ref "U72") (pin "20") (pinfunction "VIN2_20") (pintype "passive"))
    )
    (net (code "2") (name "+3V3_RX_ISO") (class "Default")
      (node (ref "C105") (pin "1") (pinfunction "1_1") (pintype "passive"))
      (node (ref "C106") (pin "1") (pinfunction "1_1") (pintype "passive"))
      (node (ref "C107") (pin "1") (pinfunction "1_1") (pintype "passive"))
      (node (ref "C108") (pin "1") (pinfunction "1_1") (pintype "passive"))
      (node (ref "C73") (pin "1") (pinfunction "1_1") (pintype "passive"))
      (node (ref "C74") (pin "1") (pinfunction "1_1") (pintype "passive"))
      (node (ref "C75") (pin "1") (pinfunction "1_1") (pintype "passive"))
      (node (ref "C76") (pin "1") (pinfunction "1_1") (pintype "passive"))
      (node (ref "U49") (pin "1") (pinfunction "VIN1_1") (pintype "passive"))
      (node (ref "U50") (pin "1") (pinfunction "VIN1_1") (pintype "passive"))
      (node (ref "U51") (pin "1") (pinfunction "VIN1_1") (pintype "passive"))
      (node (ref "U52") (pin "1") (pinfunction "VIN1_1") (pintype "passive"))
      (node (ref "U69") (pin "1") (pinfunction "VIN1_1") (pintype "passive"))
      (node (ref "U70") (pin "1") (pinfunction "VIN1_1") (pintype "passive"))
      (node (ref "U71") (pin "1") (pinfunction "VIN1_1") (pintype "passive"))
      (node (ref "U72") (pin "1") (pinfunction "VIN1_1") (pintype "passive"))
    )
    (net (code "3") (name "/RX1_ISO_N") (class "Default")
      (node (ref "CN9") (pin "2") (pinfunction "2_2") (pintype "passive"))
      (node (ref "R33") (pin "1") (pinfunction "1_1") (pintype "passive"))
      (node (ref "U41") (pin "2") (pinfunction "D-_2") (pintype "passive"))
      (node (ref "U49") (pin "6") (pinfunction "DIN1-_6") (pintype "passive"))
    )
    (net (code "4") (name "/RX1_ISO_P") (class "Default")
      (node (ref "CN9") (pin "1") (pinfunction "1_1") (pintype "passive"))
      (node (ref "R33") (pin "2") (pinfunction "2_2") (pintype "passive"))
      (node (ref "U41") (pin "1") (pinfunction "D+_1") (pintype "passive"))
      (node (ref "U49") (pin "5") (pinfunction "DIN1+_5") (pintype "passive"))
    )
    (net (code "5") (name "/RX1_N") (class "Default")
      (node (ref "CN11") (pin "2") (pinfunction "2_2") (pintype "passive"))
      (node (ref "R41") (pin "1") (pinfunction "1_1") (pintype "passive"))
      (node (ref "U49") (pin "15") (pinfunction "DOUT1-_15") (pintype "passive"))
      (node (ref "U53") (pin "1") (pinfunction "D+_1") (pintype "passive"))
    )
    (net (code "6") (name "/RX1_P") (class "Default")
      (node (ref "CN11") (pin "1") (pinfunction "1_1") (pintype "passive"))
      (node (ref "R41") (pin "2") (pinfunction "2_2") (pintype "passive"))
      (node (ref "U49") (pin "16") (pinfunction "DOUT1+_16") (pintype "passive"))
      (node (ref "U53") (pin "2") (pinfunction "D-_2") (pintype "passive"))
    )
    (net (code "7") (name "/RX2_ISO_N") (class "Default")
      (node (ref "CN9") (pin "4") (pinfunction "4_4") (pintype "passive"))
      (node (ref "R34") (pin "1") (pinfunction "1_1") (pintype "passive"))
      (node (ref "U42") (pin "2") (pinfunction "D-_2") (pintype "passive"))
      (node (ref "U49") (pin "8") (pinfunction "DIN2-_8") (pintype "passive"))
    )
    (net (code "8") (name "/RX2_ISO_P") (class "Default")
      (node (ref "CN9") (pin "3") (pinfunction "3_3") (pintype "passive"))
      (node (ref "R34") (pin "2") (pinfunction "2_2") (pintype "passive"))
      (node (ref "U42") (pin "1") (pinfunction "D+_1") (pintype "passive"))
      (node (ref "U49") (pin "7") (pinfunction "DIN2+_7") (pintype "passive"))
    )
    (net (code "9") (name "/RX2_N") (class "Default")
      (node (ref "CN11") (pin "4") (pinfunction "4_4") (pintype "passive"))
      (node (ref "R42") (pin "1") (pinfunction "1_1") (pintype "passive"))
      (node (ref "U49") (pin "13") (pinfunction "DOUT2-_13") (pintype "passive"))
      (node (ref "U54") (pin "1") (pinfunction "D+_1") (pintype "passive"))
    )
    (net (code "10") (name "/RX2_P") (class "Default")
      (node (ref "CN11") (pin "3") (pinfunction "3_3") (pintype "passive"))
      (node (ref "R42") (pin "2") (pinfunction "2_2") (pintype "passive"))
      (node (ref "U49") (pin "14") (pinfunction "DOUT2+_14") (pintype "passive"))
      (node (ref "U54") (pin "2") (pinfunction "D-_2") (pintype "passive"))
    )
    (net (code "11") (name "/RX3_ISO_N") (class "Default")
      (node (ref "CN9") (pin "8") (pinfunction "8_8") (pintype "passive"))
      (node (ref "R35") (pin "1") (pinfunction "1_1") (pintype "passive"))
      (node (ref "U43") (pin "2") (pinfunction "D-_2") (pintype "passive"))
      (node (ref "U50") (pin "6") (pinfunction "DIN1-_6") (pintype "passive"))
    )
    (net (code "12") (name "/RX3_ISO_P") (class "Default")
      (node (ref "CN9") (pin "7") (pinfunction "7_7") (pintype "passive"))
      (node (ref "R35") (pin "2") (pinfunction "2_2") (pintype "passive"))
      (node (ref "U43") (pin "1") (pinfunction "D+_1") (pintype "passive"))
      (node (ref "U50") (pin "5") (pinfunction "DIN1+_5") (pintype "passive"))
    )
    (net (code "13") (name "/RX3_N") (class "Default")
      (node (ref "CN11") (pin "8") (pinfunction "8_8") (pintype "passive"))
      (node (ref "R43") (pin "1") (pinfunction "1_1") (pintype "passive"))
      (node (ref "U50") (pin "15") (pinfunction "DOUT1-_15") (pintype "passive"))
      (node (ref "U55") (pin "1") (pinfunction "D+_1") (pintype "passive"))
    )
    (net (code "14") (name "/RX3_P") (class "Default")
      (node (ref "CN11") (pin "7") (pinfunction "7_7") (pintype "passive"))
      (node (ref "R43") (pin "2") (pinfunction "2_2") (pintype "passive"))
      (node (ref "U50") (pin "16") (pinfunction "DOUT1+_16") (pintype "passive"))
      (node (ref "U55") (pin "2") (pinfunction "D-_2") (pintype "passive"))
    )
    (net (code "15") (name "/RX4_ISO_N") (class "Default")
      (node (ref "CN9") (pin "10") (pinfunction "10_10") (pintype "passive"))
      (node (ref "R36") (pin "1") (pinfunction "1_1") (pintype "passive"))
      (node (ref "U44") (pin "2") (pinfunction "D-_2") (pintype "passive"))
      (node (ref "U50") (pin "8") (pinfunction "DIN2-_8") (pintype "passive"))
    )
    (net (code "16") (name "/RX4_ISO_P") (class "Default")
      (node (ref "CN9") (pin "9") (pinfunction "9_9") (pintype "passive"))
      (node (ref "R36") (pin "2") (pinfunction "2_2") (pintype "passive"))
      (node (ref "U44") (pin "1") (pinfunction "D+_1") (pintype "passive"))
      (node (ref "U50") (pin "7") (pinfunction "DIN2+_7") (pintype "passive"))
    )
    (net (code "17") (name "/RX4_N") (class "Default")
      (node (ref "CN11") (pin "10") (pinfunction "10_10") (pintype "passive"))
      (node (ref "R44") (pin "1") (pinfunction "1_1") (pintype "passive"))
      (node (ref "U50") (pin "13") (pinfunction "DOUT2-_13") (pintype "passive"))
      (node (ref "U56") (pin "1") (pinfunction "D+_1") (pintype "passive"))
    )
    (net (code "18") (name "/RX4_P") (class "Default")
      (node (ref "CN11") (pin "9") (pinfunction "9_9") (pintype "passive"))
      (node (ref "R44") (pin "2") (pinfunction "2_2") (pintype "passive"))
      (node (ref "U50") (pin "14") (pinfunction "DOUT2+_14") (pintype "passive"))
      (node (ref "U56") (pin "2") (pinfunction "D-_2") (pintype "passive"))
    )
    (net (code "19") (name "/RX5_ISO_N") (class "Default")
      (node (ref "CN10") (pin "2") (pinfunction "2_2") (pintype "passive"))
      (node (ref "R37") (pin "1") (pinfunction "1_1") (pintype "passive"))
      (node (ref "U45") (pin "2") (pinfunction "D-_2") (pintype "passive"))
      (node (ref "U51") (pin "6") (pinfunction "DIN1-_6") (pintype "passive"))
    )
    (net (code "20") (name "/RX5_ISO_P") (class "Default")
      (node (ref "CN10") (pin "1") (pinfunction "1_1") (pintype "passive"))
      (node (ref "R37") (pin "2") (pinfunction "2_2") (pintype "passive"))
      (node (ref "U45") (pin "1") (pinfunction "D+_1") (pintype "passive"))
      (node (ref "U51") (pin "5") (pinfunction "DIN1+_5") (pintype "passive"))
    )
    (net (code "21") (name "/RX5_N") (class "Default")
      (node (ref "CN12") (pin "2") (pinfunction "2_2") (pintype "passive"))
      (node (ref "R45") (pin "1") (pinfunction "1_1") (pintype "passive"))
      (node (ref "U51") (pin "15") (pinfunction "DOUT1-_15") (pintype "passive"))
      (node (ref "U57") (pin "1") (pinfunction "D+_1") (pintype "passive"))
    )
    (net (code "22") (name "/RX5_P") (class "Default")
      (node (ref "CN12") (pin "1") (pinfunction "1_1") (pintype "passive"))
      (node (ref "R45") (pin "2") (pinfunction "2_2") (pintype "passive"))
      (node (ref "U51") (pin "16") (pinfunction "DOUT1+_16") (pintype "passive"))
      (node (ref "U57") (pin "2") (pinfunction "D-_2") (pintype "passive"))
    )
    (net (code "23") (name "/RX6_ISO_N") (class "Default")
      (node (ref "CN10") (pin "4") (pinfunction "4_4") (pintype "passive"))
      (node (ref "R38") (pin "1") (pinfunction "1_1") (pintype "passive"))
      (node (ref "U46") (pin "2") (pinfunction "D-_2") (pintype "passive"))
      (node (ref "U51") (pin "8") (pinfunction "DIN2-_8") (pintype "passive"))
    )
    (net (code "24") (name "/RX6_ISO_P") (class "Default")
      (node (ref "CN10") (pin "3") (pinfunction "3_3") (pintype "passive"))
      (node (ref "R38") (pin "2") (pinfunction "2_2") (pintype "passive"))
      (node (ref "U46") (pin "1") (pinfunction "D+_1") (pintype "passive"))
      (node (ref "U51") (pin "7") (pinfunction "DIN2+_7") (pintype "passive"))
    )
    (net (code "25") (name "/RX6_N") (class "Default")
      (node (ref "CN12") (pin "4") (pinfunction "4_4") (pintype "passive"))
      (node (ref "R46") (pin "1") (pinfunction "1_1") (pintype "passive"))
      (node (ref "U51") (pin "13") (pinfunction "DOUT2-_13") (pintype "passive"))
      (node (ref "U58") (pin "1") (pinfunction "D+_1") (pintype "passive"))
    )
    (net (code "26") (name "/RX6_P") (class "Default")
      (node (ref "CN12") (pin "3") (pinfunction "3_3") (pintype "passive"))
      (node (ref "R46") (pin "2") (pinfunction "2_2") (pintype "passive"))
      (node (ref "U51") (pin "14") (pinfunction "DOUT2+_14") (pintype "passive"))
      (node (ref "U58") (pin "2") (pinfunction "D-_2") (pintype "passive"))
    )
    (net (code "27") (name "/RX7_ISO_N") (class "Default")
      (node (ref "CN10") (pin "8") (pinfunction "8_8") (pintype "passive"))
      (node (ref "R39") (pin "1") (pinfunction "1_1") (pintype "passive"))
      (node (ref "U47") (pin "2") (pinfunction "D-_2") (pintype "passive"))
      (node (ref "U52") (pin "6") (pinfunction "DIN1-_6") (pintype "passive"))
    )
    (net (code "28") (name "/RX7_ISO_P") (class "Default")
      (node (ref "CN10") (pin "7") (pinfunction "7_7") (pintype "passive"))
      (node (ref "R39") (pin "2") (pinfunction "2_2") (pintype "passive"))
      (node (ref "U47") (pin "1") (pinfunction "D+_1") (pintype "passive"))
      (node (ref "U52") (pin "5") (pinfunction "DIN1+_5") (pintype "passive"))
    )
    (net (code "29") (name "/RX7_N") (class "Default")
      (node (ref "CN12") (pin "8") (pinfunction "8_8") (pintype "passive"))
      (node (ref "R47") (pin "1") (pinfunction "1_1") (pintype "passive"))
      (node (ref "U52") (pin "15") (pinfunction "DOUT1-_15") (pintype "passive"))
      (node (ref "U59") (pin "1") (pinfunction "D+_1") (pintype "passive"))
    )
    (net (code "30") (name "/RX7_P") (class "Default")
      (node (ref "CN12") (pin "7") (pinfunction "7_7") (pintype "passive"))
      (node (ref "R47") (pin "2") (pinfunction "2_2") (pintype "passive"))
      (node (ref "U52") (pin "16") (pinfunction "DOUT1+_16") (pintype "passive"))
      (node (ref "U59") (pin "2") (pinfunction "D-_2") (pintype "passive"))
    )
    (net (code "31") (name "/RX8_ISO_N") (class "Default")
      (node (ref "CN10") (pin "10") (pinfunction "10_10") (pintype "passive"))
      (node (ref "R40") (pin "1") (pinfunction "1_1") (pintype "passive"))
      (node (ref "U48") (pin "2") (pinfunction "D-_2") (pintype "passive"))
      (node (ref "U52") (pin "8") (pinfunction "DIN2-_8") (pintype "passive"))
    )
    (net (code "32") (name "/RX8_ISO_P") (class "Default")
      (node (ref "CN10") (pin "9") (pinfunction "9_9") (pintype "passive"))
      (node (ref "R40") (pin "2") (pinfunction "2_2") (pintype "passive"))
      (node (ref "U48") (pin "1") (pinfunction "D+_1") (pintype "passive"))
      (node (ref "U52") (pin "7") (pinfunction "DIN2+_7") (pintype "passive"))
    )
    (net (code "33") (name "/RX8_N") (class "Default")
      (node (ref "CN12") (pin "10") (pinfunction "10_10") (pintype "passive"))
      (node (ref "R48") (pin "1") (pinfunction "1_1") (pintype "passive"))
      (node (ref "U52") (pin "13") (pinfunction "DOUT2-_13") (pintype "passive"))
      (node (ref "U60") (pin "1") (pinfunction "D+_1") (pintype "passive"))
    )
    (net (code "34") (name "/RX8_P") (class "Default")
      (node (ref "CN12") (pin "9") (pinfunction "9_9") (pintype "passive"))
      (node (ref "R48") (pin "2") (pinfunction "2_2") (pintype "passive"))
      (node (ref "U52") (pin "14") (pinfunction "DOUT2+_14") (pintype "passive"))
      (node (ref "U60") (pin "2") (pinfunction "D-_2") (pintype "passive"))
    )
    (net (code "35") (name "/RX9_ISO_N") (class "Default")
      (node (ref "CN13") (pin "2") (pinfunction "2_2") (pintype "passive"))
      (node (ref "R49") (pin "1") (pinfunction "1_1") (pintype "passive"))
      (node (ref "U61") (pin "2") (pinfunction "D-_2") (pintype "passive"))
      (node (ref "U69") (pin "6") (pinfunction "DIN1-_6") (pintype "passive"))
    )
    (net (code "36") (name "/RX9_ISO_P") (class "Default")
      (node (ref "CN13") (pin "1") (pinfunction "1_1") (pintype "passive"))
      (node (ref "R49") (pin "2") (pinfunction "2_2") (pintype "passive"))
      (node (ref "U61") (pin "1") (pinfunction "D+_1") (pintype "passive"))
      (node (ref "U69") (pin "5") (pinfunction "DIN1+_5") (pintype "passive"))
    )
    (net (code "37") (name "/RX9_N") (class "Default")
      (node (ref "CN15") (pin "2") (pinfunction "2_2") (pintype "passive"))
      (node (ref "R57") (pin "1") (pinfunction "1_1") (pintype "passive"))
      (node (ref "U69") (pin "15") (pinfunction "DOUT1-_15") (pintype "passive"))
      (node (ref "U73") (pin "1") (pinfunction "D+_1") (pintype "passive"))
    )
    (net (code "38") (name "/RX9_P") (class "Default")
      (node (ref "CN15") (pin "1") (pinfunction "1_1") (pintype "passive"))
      (node (ref "R57") (pin "2") (pinfunction "2_2") (pintype "passive"))
      (node (ref "U69") (pin "16") (pinfunction "DOUT1+_16") (pintype "passive"))
      (node (ref "U73") (pin "2") (pinfunction "D-_2") (pintype "passive"))
    )
    (net (code "39") (name "/RX10_ISO_N") (class "Default")
      (node (ref "CN13") (pin "4") (pinfunction "4_4") (pintype "passive"))
      (node (ref "R50") (pin "1") (pinfunction "1_1") (pintype "passive"))
      (node (ref "U62") (pin "2") (pinfunction "D-_2") (pintype "passive"))
      (node (ref "U69") (pin "8") (pinfunction "DIN2-_8") (pintype "passive"))
    )
    (net (code "40") (name "/RX10_ISO_P") (class "Default")
      (node (ref "CN13") (pin "3") (pinfunction "3_3") (pintype "passive"))
      (node (ref "R50") (pin "2") (pinfunction "2_2") (pintype "passive"))
      (node (ref "U62") (pin "1") (pinfunction "D+_1") (pintype "passive"))
      (node (ref "U69") (pin "7") (pinfunction "DIN2+_7") (pintype "passive"))
    )
    (net (code "41") (name "/RX10_N") (class "Default")
      (node (ref "CN15") (pin "4") (pinfunction "4_4") (pintype "passive"))
      (node (ref "R58") (pin "1") (pinfunction "1_1") (pintype "passive"))
      (node (ref "U69") (pin "13") (pinfunction "DOUT2-_13") (pintype "passive"))
      (node (ref "U74") (pin "1") (pinfunction "D+_1") (pintype "passive"))
    )
    (net (code "42") (name "/RX10_P") (class "Default")
      (node (ref "CN15") (pin "3") (pinfunction "3_3") (pintype "passive"))
      (node (ref "R58") (pin "2") (pinfunction "2_2") (pintype "passive"))
      (node (ref "U69") (pin "14") (pinfunction "DOUT2+_14") (pintype "passive"))
      (node (ref "U74") (pin "2") (pinfunction "D-_2") (pintype "passive"))
    )
    (net (code "43") (name "/RX11_ISO_N") (class "Default")
      (node (ref "CN13") (pin "8") (pinfunction "8_8") (pintype "passive"))
      (node (ref "R51") (pin "1") (pinfunction "1_1") (pintype "passive"))
      (node (ref "U63") (pin "2") (pinfunction "D-_2") (pintype "passive"))
      (node (ref "U70") (pin "6") (pinfunction "DIN1-_6") (pintype "passive"))
    )
    (net (code "44") (name "/RX11_ISO_P") (class "Default")
      (node (ref "CN13") (pin "7") (pinfunction "7_7") (pintype "passive"))
      (node (ref "R51") (pin "2") (pinfunction "2_2") (pintype "passive"))
      (node (ref "U63") (pin "1") (pinfunction "D+_1") (pintype "passive"))
      (node (ref "U70") (pin "5") (pinfunction "DIN1+_5") (pintype "passive"))
    )
    (net (code "45") (name "/RX11_N") (class "Default")
      (node (ref "CN15") (pin "8") (pinfunction "8_8") (pintype "passive"))
      (node (ref "R59") (pin "1") (pinfunction "1_1") (pintype "passive"))
      (node (ref "U70") (pin "15") (pinfunction "DOUT1-_15") (pintype "passive"))
      (node (ref "U75") (pin "1") (pinfunction "D+_1") (pintype "passive"))
    )
    (net (code "46") (name "/RX11_P") (class "Default")
      (node (ref "CN15") (pin "7") (pinfunction "7_7") (pintype "passive"))
      (node (ref "R59") (pin "2") (pinfunction "2_2") (pintype "passive"))
      (node (ref "U70") (pin "16") (pinfunction "DOUT1+_16") (pintype "passive"))
      (node (ref "U75") (pin "2") (pinfunction "D-_2") (pintype "passive"))
    )
    (net (code "47") (name "/RX12_ISO_N") (class "Default")
      (node (ref "CN13") (pin "10") (pinfunction "10_10") (pintype "passive"))
      (node (ref "R52") (pin "1") (pinfunction "1_1") (pintype "passive"))
      (node (ref "U64") (pin "2") (pinfunction "D-_2") (pintype "passive"))
      (node (ref "U70") (pin "8") (pinfunction "DIN2-_8") (pintype "passive"))
    )
    (net (code "48") (name "/RX12_ISO_P") (class "Default")
      (node (ref "CN13") (pin "9") (pinfunction "9_9") (pintype "passive"))
      (node (ref "R52") (pin "2") (pinfunction "2_2") (pintype "passive"))
      (node (ref "U64") (pin "1") (pinfunction "D+_1") (pintype "passive"))
      (node (ref "U70") (pin "7") (pinfunction "DIN2+_7") (pintype "passive"))
    )
    (net (code "49") (name "/RX12_N") (class "Default")
      (node (ref "CN15") (pin "10") (pinfunction "10_10") (pintype "passive"))
      (node (ref "R60") (pin "1") (pinfunction "1_1") (pintype "passive"))
      (node (ref "U70") (pin "13") (pinfunction "DOUT2-_13") (pintype "passive"))
      (node (ref "U76") (pin "1") (pinfunction "D+_1") (pintype "passive"))
    )
    (net (code "50") (name "/RX12_P") (class "Default")
      (node (ref "CN15") (pin "9") (pinfunction "9_9") (pintype "passive"))
      (node (ref "R60") (pin "2") (pinfunction "2_2") (pintype "passive"))
      (node (ref "U70") (pin "14") (pinfunction "DOUT2+_14") (pintype "passive"))
      (node (ref "U76") (pin "2") (pinfunction "D-_2") (pintype "passive"))
    )
    (net (code "51") (name "/RX13_ISO_N") (class "Default")
      (node (ref "CN14") (pin "2") (pinfunction "2_2") (pintype "passive"))
      (node (ref "R53") (pin "1") (pinfunction "1_1") (pintype "passive"))
      (node (ref "U65") (pin "2") (pinfunction "D-_2") (pintype "passive"))
      (node (ref "U71") (pin "6") (pinfunction "DIN1-_6") (pintype "passive"))
    )
    (net (code "52") (name "/RX13_ISO_P") (class "Default")
      (node (ref "CN14") (pin "1") (pinfunction "1_1") (pintype "passive"))
      (node (ref "R53") (pin "2") (pinfunction "2_2") (pintype "passive"))
      (node (ref "U65") (pin "1") (pinfunction "D+_1") (pintype "passive"))
      (node (ref "U71") (pin "5") (pinfunction "DIN1+_5") (pintype "passive"))
    )
    (net (code "53") (name "/RX13_N") (class "Default")
      (node (ref "CN16") (pin "2") (pinfunction "2_2") (pintype "passive"))
      (node (ref "R61") (pin "1") (pinfunction "1_1") (pintype "passive"))
      (node (ref "U71") (pin "15") (pinfunction "DOUT1-_15") (pintype "passive"))
      (node (ref "U77") (pin "1") (pinfunction "D+_1") (pintype "passive"))
    )
    (net (code "54") (name "/RX13_P") (class "Default")
      (node (ref "CN16") (pin "1") (pinfunction "1_1") (pintype "passive"))
      (node (ref "R61") (pin "2") (pinfunction "2_2") (pintype "passive"))
      (node (ref "U71") (pin "16") (pinfunction "DOUT1+_16") (pintype "passive"))
      (node (ref "U77") (pin "2") (pinfunction "D-_2") (pintype "passive"))
    )
    (net (code "55") (name "/RX14_ISO_N") (class "Default")
      (node (ref "CN14") (pin "4") (pinfunction "4_4") (pintype "passive"))
      (node (ref "R54") (pin "1") (pinfunction "1_1") (pintype "passive"))
      (node (ref "U66") (pin "2") (pinfunction "D-_2") (pintype "passive"))
      (node (ref "U71") (pin "8") (pinfunction "DIN2-_8") (pintype "passive"))
    )
    (net (code "56") (name "/RX14_ISO_P") (class "Default")
      (node (ref "CN14") (pin "3") (pinfunction "3_3") (pintype "passive"))
      (node (ref "R54") (pin "2") (pinfunction "2_2") (pintype "passive"))
      (node (ref "U66") (pin "1") (pinfunction "D+_1") (pintype "passive"))
      (node (ref "U71") (pin "7") (pinfunction "DIN2+_7") (pintype "passive"))
    )
    (net (code "57") (name "/RX14_N") (class "Default")
      (node (ref "CN16") (pin "4") (pinfunction "4_4") (pintype "passive"))
      (node (ref "R62") (pin "1") (pinfunction "1_1") (pintype "passive"))
      (node (ref "U71") (pin "13") (pinfunction "DOUT2-_13") (pintype "passive"))
      (node (ref "U78") (pin "1") (pinfunction "D+_1") (pintype "passive"))
    )
    (net (code "58") (name "/RX14_P") (class "Default")
      (node (ref "CN16") (pin "3") (pinfunction "3_3") (pintype "passive"))
      (node (ref "R62") (pin "2") (pinfunction "2_2") (pintype "passive"))
      (node (ref "U71") (pin "14") (pinfunction "DOUT2+_14") (pintype "passive"))
      (node (ref "U78") (pin "2") (pinfunction "D-_2") (pintype "passive"))
    )
    (net (code "59") (name "/RX15_ISO_N") (class "Default")
      (node (ref "CN14") (pin "8") (pinfunction "8_8") (pintype "passive"))
      (node (ref "R55") (pin "1") (pinfunction "1_1") (pintype "passive"))
      (node (ref "U67") (pin "2") (pinfunction "D-_2") (pintype "passive"))
      (node (ref "U72") (pin "6") (pinfunction "DIN1-_6") (pintype "passive"))
    )
    (net (code "60") (name "/RX15_ISO_P") (class "Default")
      (node (ref "CN14") (pin "7") (pinfunction "7_7") (pintype "passive"))
      (node (ref "R55") (pin "2") (pinfunction "2_2") (pintype "passive"))
      (node (ref "U67") (pin "1") (pinfunction "D+_1") (pintype "passive"))
      (node (ref "U72") (pin "5") (pinfunction "DIN1+_5") (pintype "passive"))
    )
    (net (code "61") (name "/RX15_N") (class "Default")
      (node (ref "CN16") (pin "8") (pinfunction "8_8") (pintype "passive"))
      (node (ref "R63") (pin "1") (pinfunction "1_1") (pintype "passive"))
      (node (ref "U72") (pin "15") (pinfunction "DOUT1-_15") (pintype "passive"))
      (node (ref "U79") (pin "1") (pinfunction "D+_1") (pintype "passive"))
    )
    (net (code "62") (name "/RX15_P") (class "Default")
      (node (ref "CN16") (pin "7") (pinfunction "7_7") (pintype "passive"))
      (node (ref "R63") (pin "2") (pinfunction "2_2") (pintype "passive"))
      (node (ref "U72") (pin "16") (pinfunction "DOUT1+_16") (pintype "passive"))
      (node (ref "U79") (pin "2") (pinfunction "D-_2") (pintype "passive"))
    )
    (net (code "63") (name "/RX16_ISO_N") (class "Default")
      (node (ref "CN14") (pin "10") (pinfunction "10_10") (pintype "passive"))
      (node (ref "R56") (pin "1") (pinfunction "1_1") (pintype "passive"))
      (node (ref "U68") (pin "2") (pinfunction "D-_2") (pintype "passive"))
      (node (ref "U72") (pin "8") (pinfunction "DIN2-_8") (pintype "passive"))
    )
    (net (code "64") (name "/RX16_ISO_P") (class "Default")
      (node (ref "CN14") (pin "9") (pinfunction "9_9") (pintype "passive"))
      (node (ref "R56") (pin "2") (pinfunction "2_2") (pintype "passive"))
      (node (ref "U68") (pin "1") (pinfunction "D+_1") (pintype "passive"))
      (node (ref "U72") (pin "7") (pinfunction "DIN2+_7") (pintype "passive"))
    )
    (net (code "65") (name "/RX16_N") (class "Default")
      (node (ref "CN16") (pin "10") (pinfunction "10_10") (pintype "passive"))
      (node (ref "R64") (pin "1") (pinfunction "1_1") (pintype "passive"))
      (node (ref "U72") (pin "13") (pinfunction "DOUT2-_13") (pintype "passive"))
      (node (ref "U80") (pin "1") (pinfunction "D+_1") (pintype "passive"))
    )
    (net (code "66") (name "/RX16_P") (class "Default")
      (node (ref "CN16") (pin "9") (pinfunction "9_9") (pintype "passive"))
      (node (ref "R64") (pin "2") (pinfunction "2_2") (pintype "passive"))
      (node (ref "U72") (pin "14") (pinfunction "DOUT2+_14") (pintype "passive"))
      (node (ref "U80") (pin "2") (pinfunction "D-_2") (pintype "passive"))
    )
    (net (code "67") (name "GND") (class "Default")
      (node (ref "C113") (pin "1") (pinfunction "1_1") (pintype "passive"))
      (node (ref "C114") (pin "1") (pinfunction "1_1") (pintype "passive"))
      (node (ref "C115") (pin "1") (pinfunction "1_1") (pintype "passive"))
      (node (ref "C116") (pin "1") (pinfunction "1_1") (pintype "passive"))
      (node (ref "C117") (pin "1") (pinfunction "1_1") (pintype "passive"))
      (node (ref "C118") (pin "1") (pinfunction "1_1") (pintype "passive"))
      (node (ref "C119") (pin "1") (pinfunction "1_1") (pintype "passive"))
      (node (ref "C120") (pin "1") (pinfunction "1_1") (pintype "passive"))
      (node (ref "C121") (pin "1") (pinfunction "1_1") (pintype "passive"))
      (node (ref "C122") (pin "1") (pinfunction "1_1") (pintype "passive"))
      (node (ref "C123") (pin "1") (pinfunction "1_1") (pintype "passive"))
      (node (ref "C124") (pin "1") (pinfunction "1_1") (pintype "passive"))
      (node (ref "C125") (pin "1") (pinfunction "1_1") (pintype "passive"))
      (node (ref "C126") (pin "1") (pinfunction "1_1") (pintype "passive"))
      (node (ref "C127") (pin "1") (pinfunction "1_1") (pintype "passive"))
      (node (ref "C128") (pin "1") (pinfunction "1_1") (pintype "passive"))
      (node (ref "C81") (pin "1") (pinfunction "1_1") (pintype "passive"))
      (node (ref "C82") (pin "1") (pinfunction "1_1") (pintype "passive"))
      (node (ref "C83") (pin "1") (pinfunction "1_1") (pintype "passive"))
      (node (ref "C84") (pin "1") (pinfunction "1_1") (pintype "passive"))
      (node (ref "C85") (pin "1") (pinfunction "1_1") (pintype "passive"))
      (node (ref "C86") (pin "1") (pinfunction "1_1") (pintype "passive"))
      (node (ref "C87") (pin "1") (pinfunction "1_1") (pintype "passive"))
      (node (ref "C88") (pin "1") (pinfunction "1_1") (pintype "passive"))
      (node (ref "C89") (pin "1") (pinfunction "1_1") (pintype "passive"))
      (node (ref "C90") (pin "1") (pinfunction "1_1") (pintype "passive"))
      (node (ref "C91") (pin "1") (pinfunction "1_1") (pintype "passive"))
      (node (ref "C92") (pin "1") (pinfunction "1_1") (pintype "passive"))
      (node (ref "C93") (pin "1") (pinfunction "1_1") (pintype "passive"))
      (node (ref "C94") (pin "1") (pinfunction "1_1") (pintype "passive"))
      (node (ref "C95") (pin "1") (pinfunction "1_1") (pintype "passive"))
      (node (ref "C96") (pin "1") (pinfunction "1_1") (pintype "passive"))
      (node (ref "CN11") (pin "11") (pinfunction "11_11") (pintype "passive"))
      (node (ref "CN11") (pin "6") (pinfunction "6_6") (pintype "passive"))
      (node (ref "CN12") (pin "11") (pinfunction "11_11") (pintype "passive"))
      (node (ref "CN12") (pin "6") (pinfunction "6_6") (pintype "passive"))
      (node (ref "CN15") (pin "11") (pinfunction "11_11") (pintype "passive"))
      (node (ref "CN15") (pin "6") (pinfunction "6_6") (pintype "passive"))
      (node (ref "CN16") (pin "11") (pinfunction "11_11") (pintype "passive"))
      (node (ref "CN16") (pin "6") (pinfunction "6_6") (pintype "passive"))
      (node (ref "U49") (pin "11") (pinfunction "GND2_11") (pintype "passive"))
      (node (ref "U49") (pin "17") (pinfunction "GND2_17") (pintype "passive"))
      (node (ref "U49") (pin "19") (pinfunction "GND2_19") (pintype "passive"))
      (node (ref "U50") (pin "11") (pinfunction "GND2_11") (pintype "passive"))
      (node (ref "U50") (pin "17") (pinfunction "GND2_17") (pintype "passive"))
      (node (ref "U50") (pin "19") (pinfunction "GND2_19") (pintype "passive"))
      (node (ref "U51") (pin "11") (pinfunction "GND2_11") (pintype "passive"))
      (node (ref "U51") (pin "17") (pinfunction "GND2_17") (pintype "passive"))
      (node (ref "U51") (pin "19") (pinfunction "GND2_19") (pintype "passive"))
      (node (ref "U52") (pin "11") (pinfunction "GND2_11") (pintype "passive"))
      (node (ref "U52") (pin "17") (pinfunction "GND2_17") (pintype "passive"))
      (node (ref "U52") (pin "19") (pinfunction "GND2_19") (pintype "passive"))
      (node (ref "U53") (pin "3") (pinfunction "GND_3") (pintype "power_in"))
      (node (ref "U54") (pin "3") (pinfunction "GND_3") (pintype "power_in"))
      (node (ref "U55") (pin "3") (pinfunction "GND_3") (pintype "power_in"))
      (node (ref "U56") (pin "3") (pinfunction "GND_3") (pintype "power_in"))
      (node (ref "U57") (pin "3") (pinfunction "GND_3") (pintype "power_in"))
      (node (ref "U58") (pin "3") (pinfunction "GND_3") (pintype "power_in"))
      (node (ref "U59") (pin "3") (pinfunction "GND_3") (pintype "power_in"))
      (node (ref "U60") (pin "3") (pinfunction "GND_3") (pintype "power_in"))
      (node (ref "U69") (pin "11") (pinfunction "GND2_11") (pintype "passive"))
      (node (ref "U69") (pin "17") (pinfunction "GND2_17") (pintype "passive"))
      (node (ref "U69") (pin "19") (pinfunction "GND2_19") (pintype "passive"))
      (node (ref "U70") (pin "11") (pinfunction "GND2_11") (pintype "passive"))
      (node (ref "U70") (pin "17") (pinfunction "GND2_17") (pintype "passive"))
      (node (ref "U70") (pin "19") (pinfunction "GND2_19") (pintype "passive"))
      (node (ref "U71") (pin "11") (pinfunction "GND2_11") (pintype "passive"))
      (node (ref "U71") (pin "17") (pinfunction "GND2_17") (pintype "passive"))
      (node (ref "U71") (pin "19") (pinfunction "GND2_19") (pintype "passive"))
      (node (ref "U72") (pin "11") (pinfunction "GND2_11") (pintype "passive"))
      (node (ref "U72") (pin "17") (pinfunction "GND2_17") (pintype "passive"))
      (node (ref "U72") (pin "19") (pinfunction "GND2_19") (pintype "passive"))
      (node (ref "U73") (pin "3") (pinfunction "GND_3") (pintype "power_in"))
      (node (ref "U74") (pin "3") (pinfunction "GND_3") (pintype "power_in"))
      (node (ref "U75") (pin "3") (pinfunction "GND_3") (pintype "power_in"))
      (node (ref "U76") (pin "3") (pinfunction "GND_3") (pintype "power_in"))
      (node (ref "U77") (pin "3") (pinfunction "GND_3") (pintype "power_in"))
      (node (ref "U78") (pin "3") (pinfunction "GND_3") (pintype "power_in"))
      (node (ref "U79") (pin "3") (pinfunction "GND_3") (pintype "power_in"))
      (node (ref "U80") (pin "3") (pinfunction "GND_3") (pintype "power_in"))
    )
    (net (code "68") (name "GND_ISO") (class "Default")
      (node (ref "C100") (pin "1") (pinfunction "1_1") (pintype "passive"))
      (node (ref "C101") (pin "1") (pinfunction "1_1") (pintype "passive"))
      (node (ref "C102") (pin "1") (pinfunction "1_1") (pintype "passive"))
      (node (ref "C103") (pin "1") (pinfunction "1_1") (pintype "passive"))
      (node (ref "C104") (pin "1") (pinfunction "1_1") (pintype "passive"))
      (node (ref "C105") (pin "2") (pinfunction "2_2") (pintype "passive"))
      (node (ref "C106") (pin "2") (pinfunction "2_2") (pintype "passive"))
      (node (ref "C107") (pin "2") (pinfunction "2_2") (pintype "passive"))
      (node (ref "C108") (pin "2") (pinfunction "2_2") (pintype "passive"))
      (node (ref "C109") (pin "1") (pinfunction "1_1") (pintype "passive"))
      (node (ref "C110") (pin "1") (pinfunction "1_1") (pintype "passive"))
      (node (ref "C111") (pin "1") (pinfunction "1_1") (pintype "passive"))
      (node (ref "C112") (pin "1") (pinfunction "1_1") (pintype "passive"))
      (node (ref "C65") (pin "1") (pinfunction "1_1") (pintype "passive"))
      (node (ref "C66") (pin "1") (pinfunction "1_1") (pintype "passive"))
      (node (ref "C67") (pin "1") (pinfunction "1_1") (pintype "passive"))
      (node (ref "C68") (pin "1") (pinfunction "1_1") (pintype "passive"))
      (node (ref "C69") (pin "1") (pinfunction "1_1") (pintype "passive"))
      (node (ref "C70") (pin "1") (pinfunction "1_1") (pintype "passive"))
      (node (ref "C71") (pin "1") (pinfunction "1_1") (pintype "passive"))
      (node (ref "C72") (pin "1") (pinfunction "1_1") (pintype "passive"))
      (node (ref "C73") (pin "2") (pinfunction "2_2") (pintype "passive"))
      (node (ref "C74") (pin "2") (pinfunction "2_2") (pintype "passive"))
      (node (ref "C75") (pin "2") (pinfunction "2_2") (pintype "passive"))
      (node (ref "C76") (pin "2") (pinfunction "2_2") (pintype "passive"))
      (node (ref "C77") (pin "1") (pinfunction "1_1") (pintype "passive"))
      (node (ref "C78") (pin "1") (pinfunction "1_1") (pintype "passive"))
      (node (ref "C79") (pin "1") (pinfunction "1_1") (pintype "passive"))
      (node (ref "C80") (pin "1") (pinfunction "1_1") (pintype "passive"))
      (node (ref "C97") (pin "1") (pinfunction "1_1") (pintype "passive"))
      (node (ref "C98") (pin "1") (pinfunction "1_1") (pintype "passive"))
      (node (ref "C99") (pin "1") (pinfunction "1_1") (pintype "passive"))
      (node (ref "CN10") (pin "11") (pinfunction "11_11") (pintype "passive"))
      (node (ref "CN10") (pin "6") (pinfunction "6_6") (pintype "passive"))
      (node (ref "CN13") (pin "11") (pinfunction "11_11") (pintype "passive"))
      (node (ref "CN13") (pin "6") (pinfunction "6_6") (pintype "passive"))
      (node (ref "CN14") (pin "11") (pinfunction "11_11") (pintype "passive"))
      (node (ref "CN14") (pin "6") (pinfunction "6_6") (pintype "passive"))
      (node (ref "CN9") (pin "11") (pinfunction "11_11") (pintype "passive"))
      (node (ref "CN9") (pin "6") (pinfunction "6_6") (pintype "passive"))
      (node (ref "U41") (pin "3") (pinfunction "GND_3") (pintype "power_in"))
      (node (ref "U42") (pin "3") (pinfunction "GND_3") (pintype "power_in"))
      (node (ref "U43") (pin "3") (pinfunction "GND_3") (pintype "power_in"))
      (node (ref "U44") (pin "3") (pinfunction "GND_3") (pintype "power_in"))
      (node (ref "U45") (pin "3") (pinfunction "GND_3") (pintype "power_in"))
      (node (ref "U46") (pin "3") (pinfunction "GND_3") (pintype "power_in"))
      (node (ref "U47") (pin "3") (pinfunction "GND_3") (pintype "power_in"))
      (node (ref "U48") (pin "3") (pinfunction "GND_3") (pintype "power_in"))
      (node (ref "U49") (pin "10") (pinfunction "GND1_10") (pintype "passive"))
      (node (ref "U49") (pin "2") (pinfunction "GND1_2") (pintype "passive"))
      (node (ref "U49") (pin "4") (pinfunction "GND1_4") (pintype "passive"))
      (node (ref "U50") (pin "10") (pinfunction "GND1_10") (pintype "passive"))
      (node (ref "U50") (pin "2") (pinfunction "GND1_2") (pintype "passive"))
      (node (ref "U50") (pin "4") (pinfunction "GND1_4") (pintype "passive"))
      (node (ref "U51") (pin "10") (pinfunction "GND1_10") (pintype "passive"))
      (node (ref "U51") (pin "2") (pinfunction "GND1_2") (pintype "passive"))
      (node (ref "U51") (pin "4") (pinfunction "GND1_4") (pintype "passive"))
      (node (ref "U52") (pin "10") (pinfunction "GND1_10") (pintype "passive"))
      (node (ref "U52") (pin "2") (pinfunction "GND1_2") (pintype "passive"))
      (node (ref "U52") (pin "4") (pinfunction "GND1_4") (pintype "passive"))
      (node (ref "U61") (pin "3") (pinfunction "GND_3") (pintype "power_in"))
      (node (ref "U62") (pin "3") (pinfunction "GND_3") (pintype "power_in"))
      (node (ref "U63") (pin "3") (pinfunction "GND_3") (pintype "power_in"))
      (node (ref "U64") (pin "3") (pinfunction "GND_3") (pintype "power_in"))
      (node (ref "U65") (pin "3") (pinfunction "GND_3") (pintype "power_in"))
      (node (ref "U66") (pin "3") (pinfunction "GND_3") (pintype "power_in"))
      (node (ref "U67") (pin "3") (pinfunction "GND_3") (pintype "power_in"))
      (node (ref "U68") (pin "3") (pinfunction "GND_3") (pintype "power_in"))
      (node (ref "U69") (pin "10") (pinfunction "GND1_10") (pintype "passive"))
      (node (ref "U69") (pin "2") (pinfunction "GND1_2") (pintype "passive"))
      (node (ref "U69") (pin "4") (pinfunction "GND1_4") (pintype "passive"))
      (node (ref "U70") (pin "10") (pinfunction "GND1_10") (pintype "passive"))
      (node (ref "U70") (pin "2") (pinfunction "GND1_2") (pintype "passive"))
      (node (ref "U70") (pin "4") (pinfunction "GND1_4") (pintype "passive"))
      (node (ref "U71") (pin "10") (pinfunction "GND1_10") (pintype "passive"))
      (node (ref "U71") (pin "2") (pinfunction "GND1_2") (pintype "passive"))
      (node (ref "U71") (pin "4") (pinfunction "GND1_4") (pintype "passive"))
      (node (ref "U72") (pin "10") (pinfunction "GND1_10") (pintype "passive"))
      (node (ref "U72") (pin "2") (pinfunction "GND1_2") (pintype "passive"))
      (node (ref "U72") (pin "4") (pinfunction "GND1_4") (pintype "passive"))
    )
    (net (code "69") (name "Net-(C65-Pad2)") (class "Default")
      (node (ref "C65") (pin "2") (pinfunction "2_2") (pintype "passive"))
      (node (ref "C69") (pin "2") (pinfunction "2_2") (pintype "passive"))
      (node (ref "C77") (pin "2") (pinfunction "2_2") (pintype "passive"))
      (node (ref "U49") (pin "3") (pinfunction "VDD1_3") (pintype "passive"))
      (node (ref "U49") (pin "9") (pinfunction "VDD1_9") (pintype "passive"))
    )
    (net (code "70") (name "Net-(C66-Pad2)") (class "Default")
      (node (ref "C66") (pin "2") (pinfunction "2_2") (pintype "passive"))
      (node (ref "C70") (pin "2") (pinfunction "2_2") (pintype "passive"))
      (node (ref "C78") (pin "2") (pinfunction "2_2") (pintype "passive"))
      (node (ref "U50") (pin "3") (pinfunction "VDD1_3") (pintype "passive"))
      (node (ref "U50") (pin "9") (pinfunction "VDD1_9") (pintype "passive"))
    )
    (net (code "71") (name "Net-(C67-Pad2)") (class "Default")
      (node (ref "C67") (pin "2") (pinfunction "2_2") (pintype "passive"))
      (node (ref "C71") (pin "2") (pinfunction "2_2") (pintype "passive"))
      (node (ref "C79") (pin "2") (pinfunction "2_2") (pintype "passive"))
      (node (ref "U51") (pin "3") (pinfunction "VDD1_3") (pintype "passive"))
      (node (ref "U51") (pin "9") (pinfunction "VDD1_9") (pintype "passive"))
    )
    (net (code "72") (name "Net-(C68-Pad2)") (class "Default")
      (node (ref "C68") (pin "2") (pinfunction "2_2") (pintype "passive"))
      (node (ref "C72") (pin "2") (pinfunction "2_2") (pintype "passive"))
      (node (ref "C80") (pin "2") (pinfunction "2_2") (pintype "passive"))
      (node (ref "U52") (pin "3") (pinfunction "VDD1_3") (pintype "passive"))
      (node (ref "U52") (pin "9") (pinfunction "VDD1_9") (pintype "passive"))
    )
    (net (code "73") (name "Net-(C85-Pad2)") (class "Default")
      (node (ref "C85") (pin "2") (pinfunction "2_2") (pintype "passive"))
      (node (ref "C89") (pin "2") (pinfunction "2_2") (pintype "passive"))
      (node (ref "C93") (pin "2") (pinfunction "2_2") (pintype "passive"))
      (node (ref "U49") (pin "12") (pinfunction "VDD2_12") (pintype "passive"))
      (node (ref "U49") (pin "18") (pinfunction "VDD2_18") (pintype "passive"))
    )
    (net (code "74") (name "Net-(C86-Pad2)") (class "Default")
      (node (ref "C86") (pin "2") (pinfunction "2_2") (pintype "passive"))
      (node (ref "C90") (pin "2") (pinfunction "2_2") (pintype "passive"))
      (node (ref "C94") (pin "2") (pinfunction "2_2") (pintype "passive"))
      (node (ref "U50") (pin "12") (pinfunction "VDD2_12") (pintype "passive"))
      (node (ref "U50") (pin "18") (pinfunction "VDD2_18") (pintype "passive"))
    )
    (net (code "75") (name "Net-(C87-Pad2)") (class "Default")
      (node (ref "C87") (pin "2") (pinfunction "2_2") (pintype "passive"))
      (node (ref "C91") (pin "2") (pinfunction "2_2") (pintype "passive"))
      (node (ref "C95") (pin "2") (pinfunction "2_2") (pintype "passive"))
      (node (ref "U51") (pin "12") (pinfunction "VDD2_12") (pintype "passive"))
      (node (ref "U51") (pin "18") (pinfunction "VDD2_18") (pintype "passive"))
    )
    (net (code "76") (name "Net-(C88-Pad2)") (class "Default")
      (node (ref "C88") (pin "2") (pinfunction "2_2") (pintype "passive"))
      (node (ref "C92") (pin "2") (pinfunction "2_2") (pintype "passive"))
      (node (ref "C96") (pin "2") (pinfunction "2_2") (pintype "passive"))
      (node (ref "U52") (pin "12") (pinfunction "VDD2_12") (pintype "passive"))
      (node (ref "U52") (pin "18") (pinfunction "VDD2_18") (pintype "passive"))
    )
    (net (code "77") (name "Net-(C100-Pad2)") (class "Default")
      (node (ref "C100") (pin "2") (pinfunction "2_2") (pintype "passive"))
      (node (ref "C104") (pin "2") (pinfunction "2_2") (pintype "passive"))
      (node (ref "C112") (pin "2") (pinfunction "2_2") (pintype "passive"))
      (node (ref "U72") (pin "3") (pinfunction "VDD1_3") (pintype "passive"))
      (node (ref "U72") (pin "9") (pinfunction "VDD1_9") (pintype "passive"))
    )
    (net (code "78") (name "Net-(C101-Pad2)") (class "Default")
      (node (ref "C101") (pin "2") (pinfunction "2_2") (pintype "passive"))
      (node (ref "C109") (pin "2") (pinfunction "2_2") (pintype "passive"))
      (node (ref "C97") (pin "2") (pinfunction "2_2") (pintype "passive"))
      (node (ref "U69") (pin "3") (pinfunction "VDD1_3") (pintype "passive"))
      (node (ref "U69") (pin "9") (pinfunction "VDD1_9") (pintype "passive"))
    )
    (net (code "79") (name "Net-(C102-Pad2)") (class "Default")
      (node (ref "C102") (pin "2") (pinfunction "2_2") (pintype "passive"))
      (node (ref "C110") (pin "2") (pinfunction "2_2") (pintype "passive"))
      (node (ref "C98") (pin "2") (pinfunction "2_2") (pintype "passive"))
      (node (ref "U70") (pin "3") (pinfunction "VDD1_3") (pintype "passive"))
      (node (ref "U70") (pin "9") (pinfunction "VDD1_9") (pintype "passive"))
    )
    (net (code "80") (name "Net-(C103-Pad2)") (class "Default")
      (node (ref "C103") (pin "2") (pinfunction "2_2") (pintype "passive"))
      (node (ref "C111") (pin "2") (pinfunction "2_2") (pintype "passive"))
      (node (ref "C99") (pin "2") (pinfunction "2_2") (pintype "passive"))
      (node (ref "U71") (pin "3") (pinfunction "VDD1_3") (pintype "passive"))
      (node (ref "U71") (pin "9") (pinfunction "VDD1_9") (pintype "passive"))
    )
    (net (code "81") (name "Net-(C117-Pad2)") (class "Default")
      (node (ref "C117") (pin "2") (pinfunction "2_2") (pintype "passive"))
      (node (ref "C121") (pin "2") (pinfunction "2_2") (pintype "passive"))
      (node (ref "C125") (pin "2") (pinfunction "2_2") (pintype "passive"))
      (node (ref "U69") (pin "12") (pinfunction "VDD2_12") (pintype "passive"))
      (node (ref "U69") (pin "18") (pinfunction "VDD2_18") (pintype "passive"))
    )
    (net (code "82") (name "Net-(C118-Pad2)") (class "Default")
      (node (ref "C118") (pin "2") (pinfunction "2_2") (pintype "passive"))
      (node (ref "C122") (pin "2") (pinfunction "2_2") (pintype "passive"))
      (node (ref "C126") (pin "2") (pinfunction "2_2") (pintype "passive"))
      (node (ref "U70") (pin "12") (pinfunction "VDD2_12") (pintype "passive"))
      (node (ref "U70") (pin "18") (pinfunction "VDD2_18") (pintype "passive"))
    )
    (net (code "83") (name "Net-(C119-Pad2)") (class "Default")
      (node (ref "C119") (pin "2") (pinfunction "2_2") (pintype "passive"))
      (node (ref "C123") (pin "2") (pinfunction "2_2") (pintype "passive"))
      (node (ref "C127") (pin "2") (pinfunction "2_2") (pintype "passive"))
      (node (ref "U71") (pin "12") (pinfunction "VDD2_12") (pintype "passive"))
      (node (ref "U71") (pin "18") (pinfunction "VDD2_18") (pintype "passive"))
    )
    (net (code "84") (name "Net-(C120-Pad2)") (class "Default")
      (node (ref "C120") (pin "2") (pinfunction "2_2") (pintype "passive"))
      (node (ref "C124") (pin "2") (pinfunction "2_2") (pintype "passive"))
      (node (ref "C128") (pin "2") (pinfunction "2_2") (pintype "passive"))
      (node (ref "U72") (pin "12") (pinfunction "VDD2_12") (pintype "passive"))
      (node (ref "U72") (pin "18") (pinfunction "VDD2_18") (pintype "passive"))
    )
    (net (code "85") (name "unconnected-(CN9-Pad5)") (class "Default")
      (node (ref "CN9") (pin "5") (pinfunction "5_5") (pintype "passive"))
    )
    (net (code "86") (name "unconnected-(CN10-Pad5)") (class "Default")
      (node (ref "CN10") (pin "5") (pinfunction "5_5") (pintype "passive"))
    )
    (net (code "87") (name "unconnected-(CN11-Pad5)") (class "Default")
      (node (ref "CN11") (pin "5") (pinfunction "5_5") (pintype "passive"))
    )
    (net (code "88") (name "unconnected-(CN12-Pad5)") (class "Default")
      (node (ref "CN12") (pin "5") (pinfunction "5_5") (pintype "passive"))
    )
    (net (code "89") (name "unconnected-(CN13-Pad5)") (class "Default")
      (node (ref "CN13") (pin "5") (pinfunction "5_5") (pintype "passive"))
    )
    (net (code "90") (name "unconnected-(CN14-Pad5)") (class "Default")
      (node (ref "CN14") (pin "5") (pinfunction "5_5") (pintype "passive"))
    )
    (net (code "91") (name "unconnected-(CN15-Pad5)") (class "Default")
      (node (ref "CN15") (pin "5") (pinfunction "5_5") (pintype "passive"))
    )
    (net (code "92") (name "unconnected-(CN16-Pad5)") (class "Default")
      (node (ref "CN16") (pin "5") (pinfunction "5_5") (pintype "passive"))
    )
  )
)
